# Mobo-v09.net
KiCad netlist of a schematic drawn in EAGLE
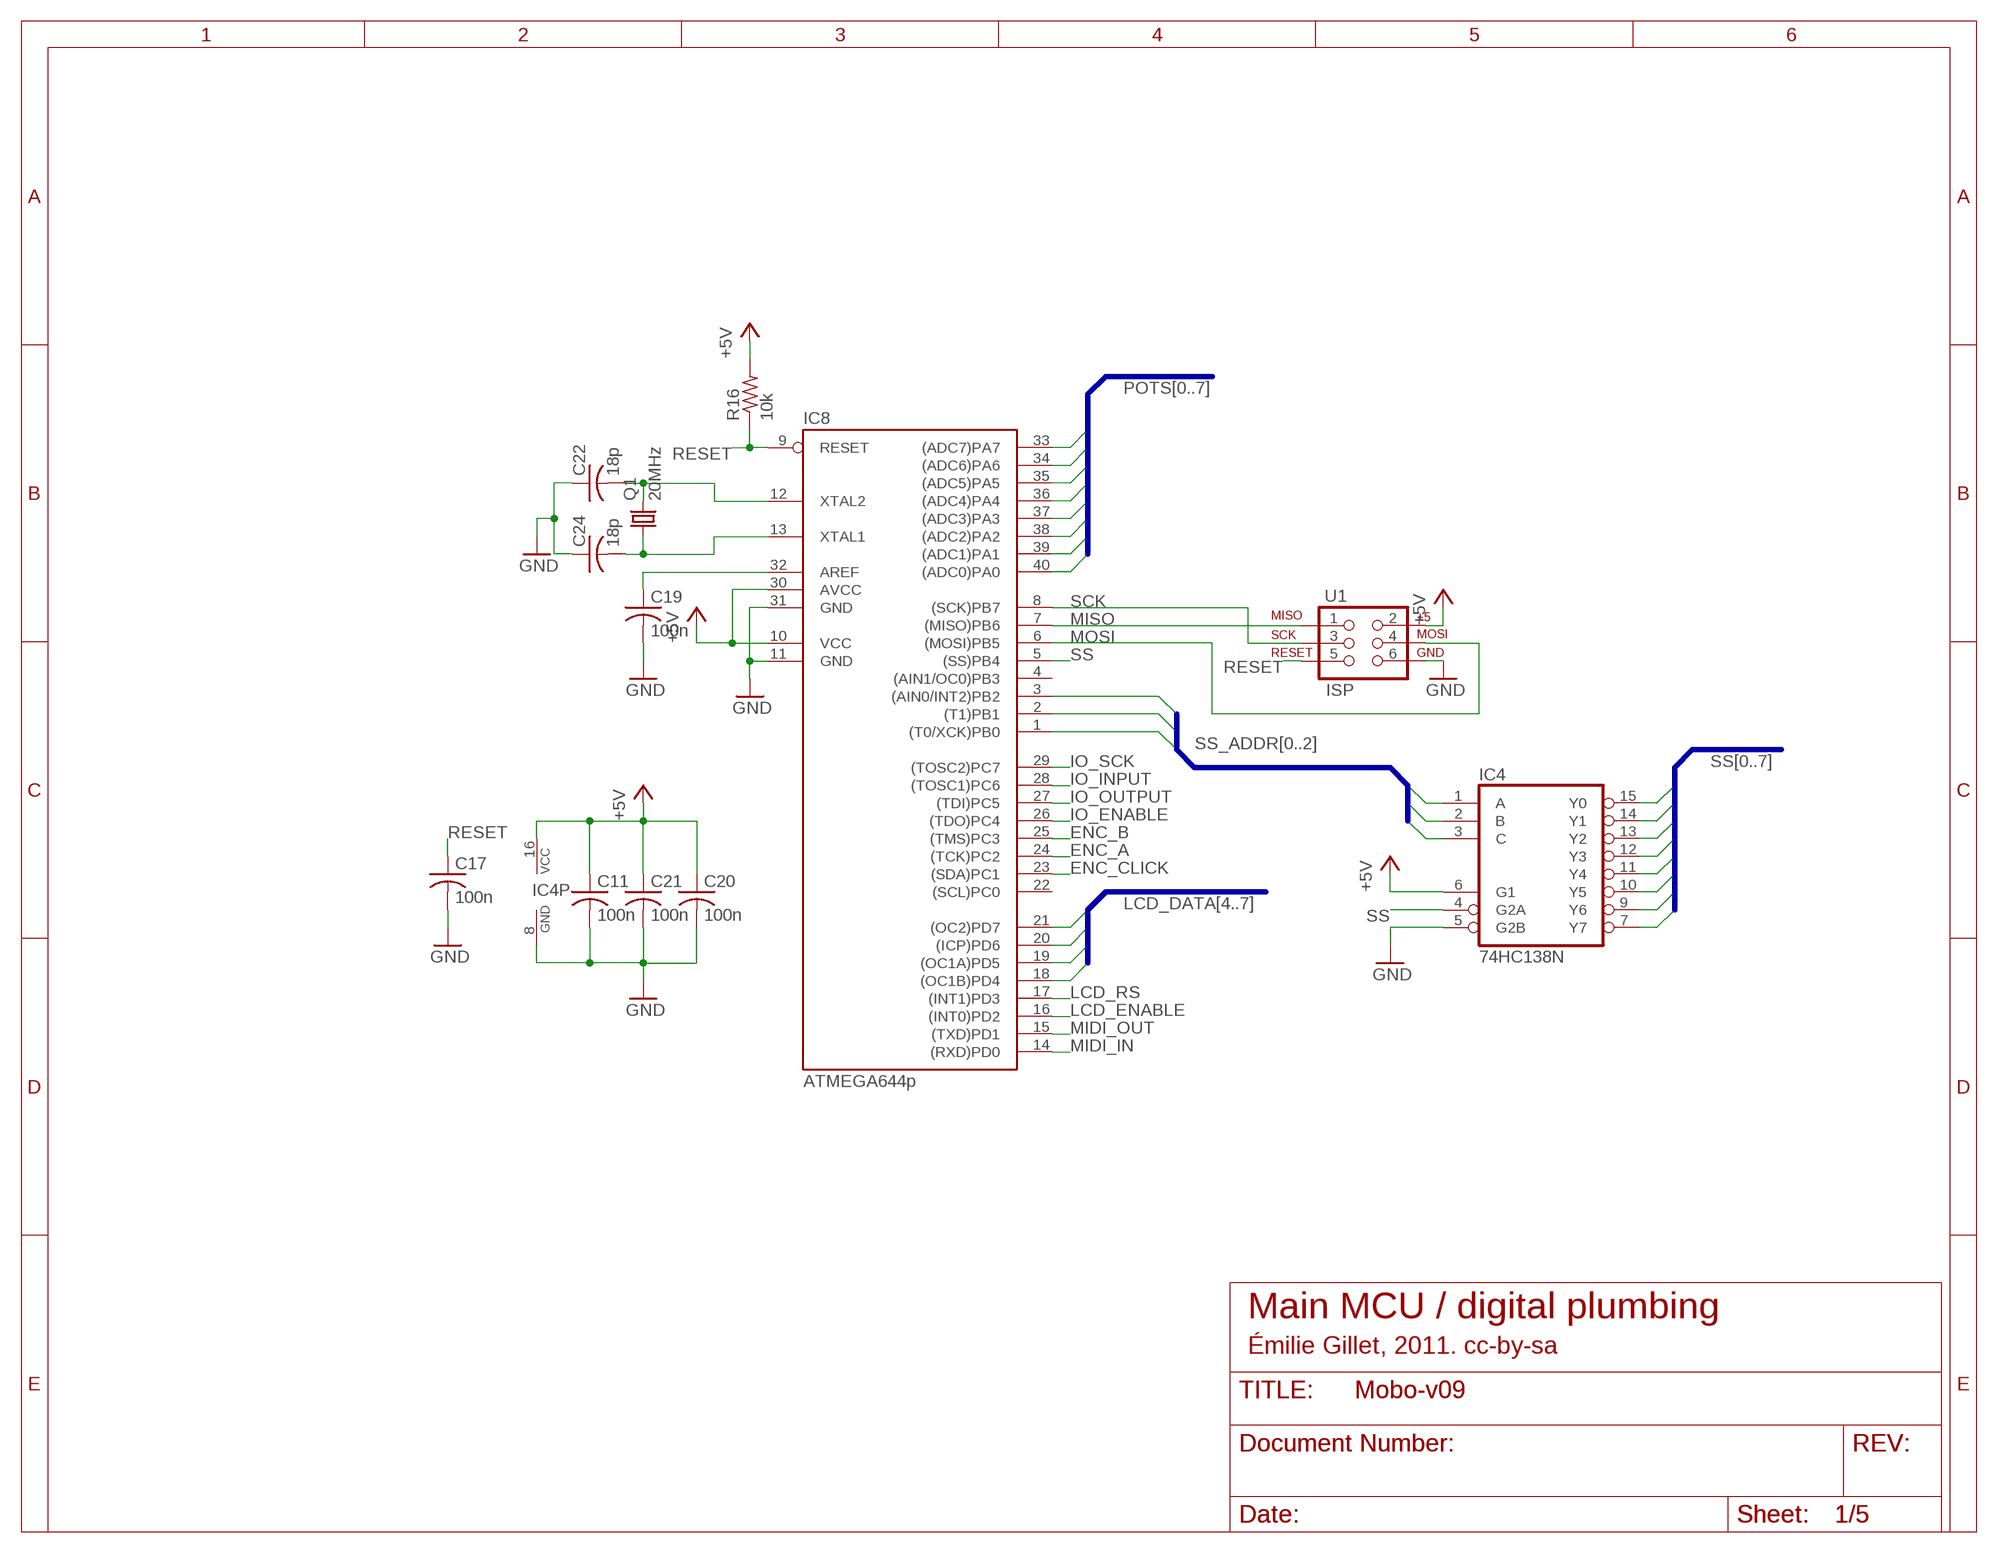
[diagram p0: schematic, sheet 1]
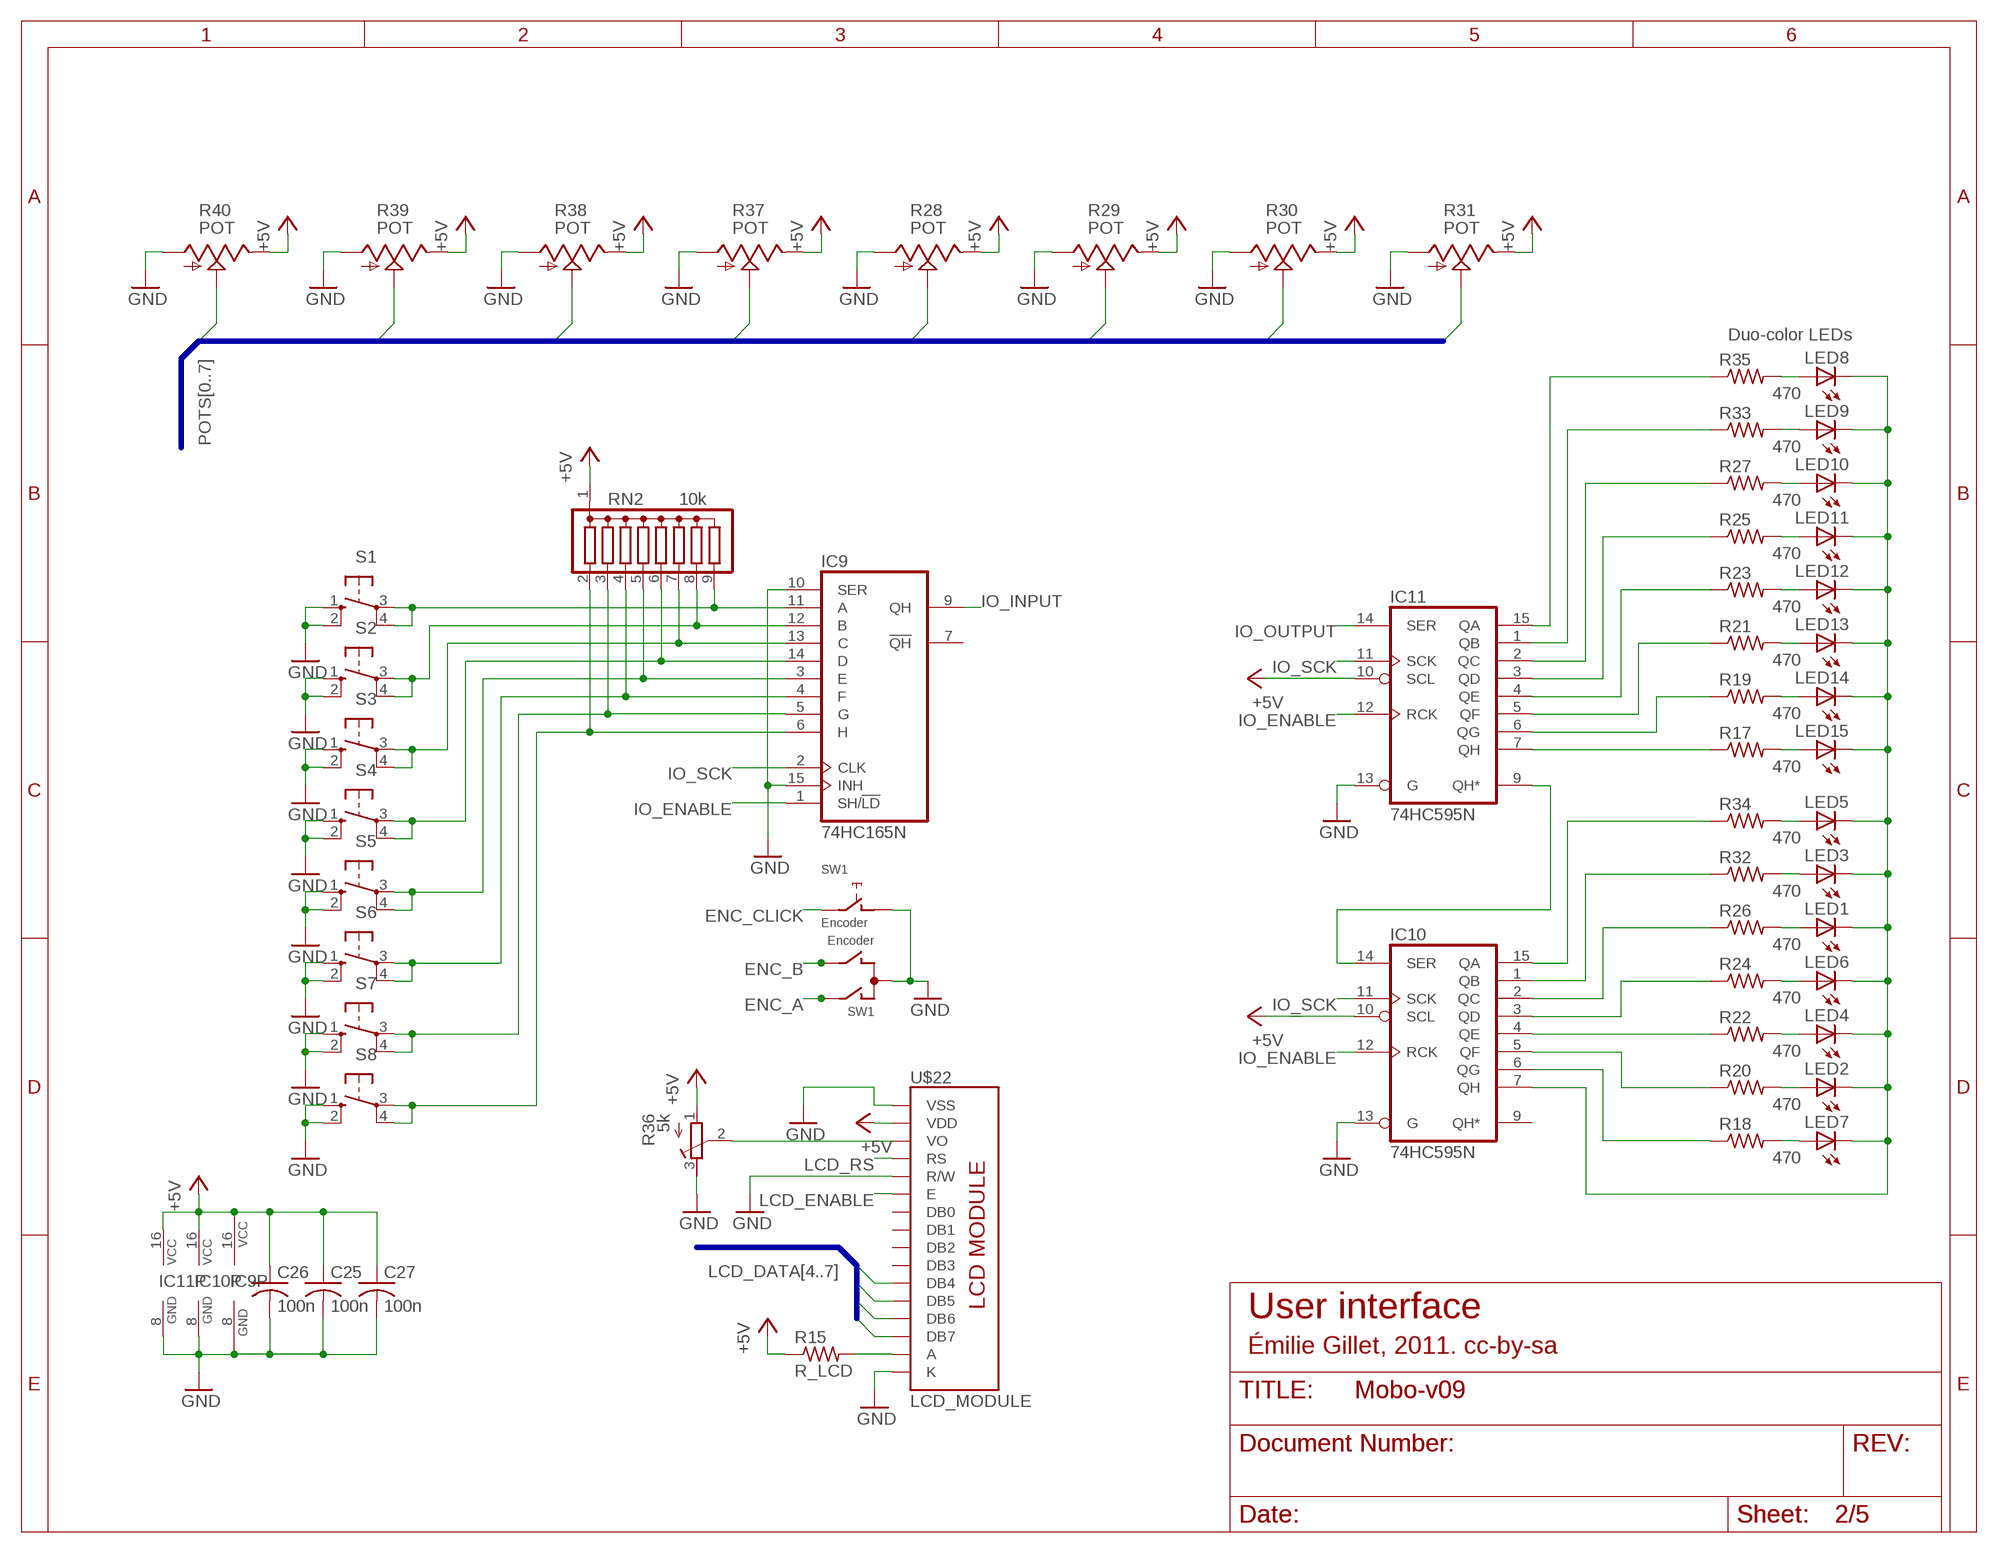
[diagram p1: schematic, sheet 2]
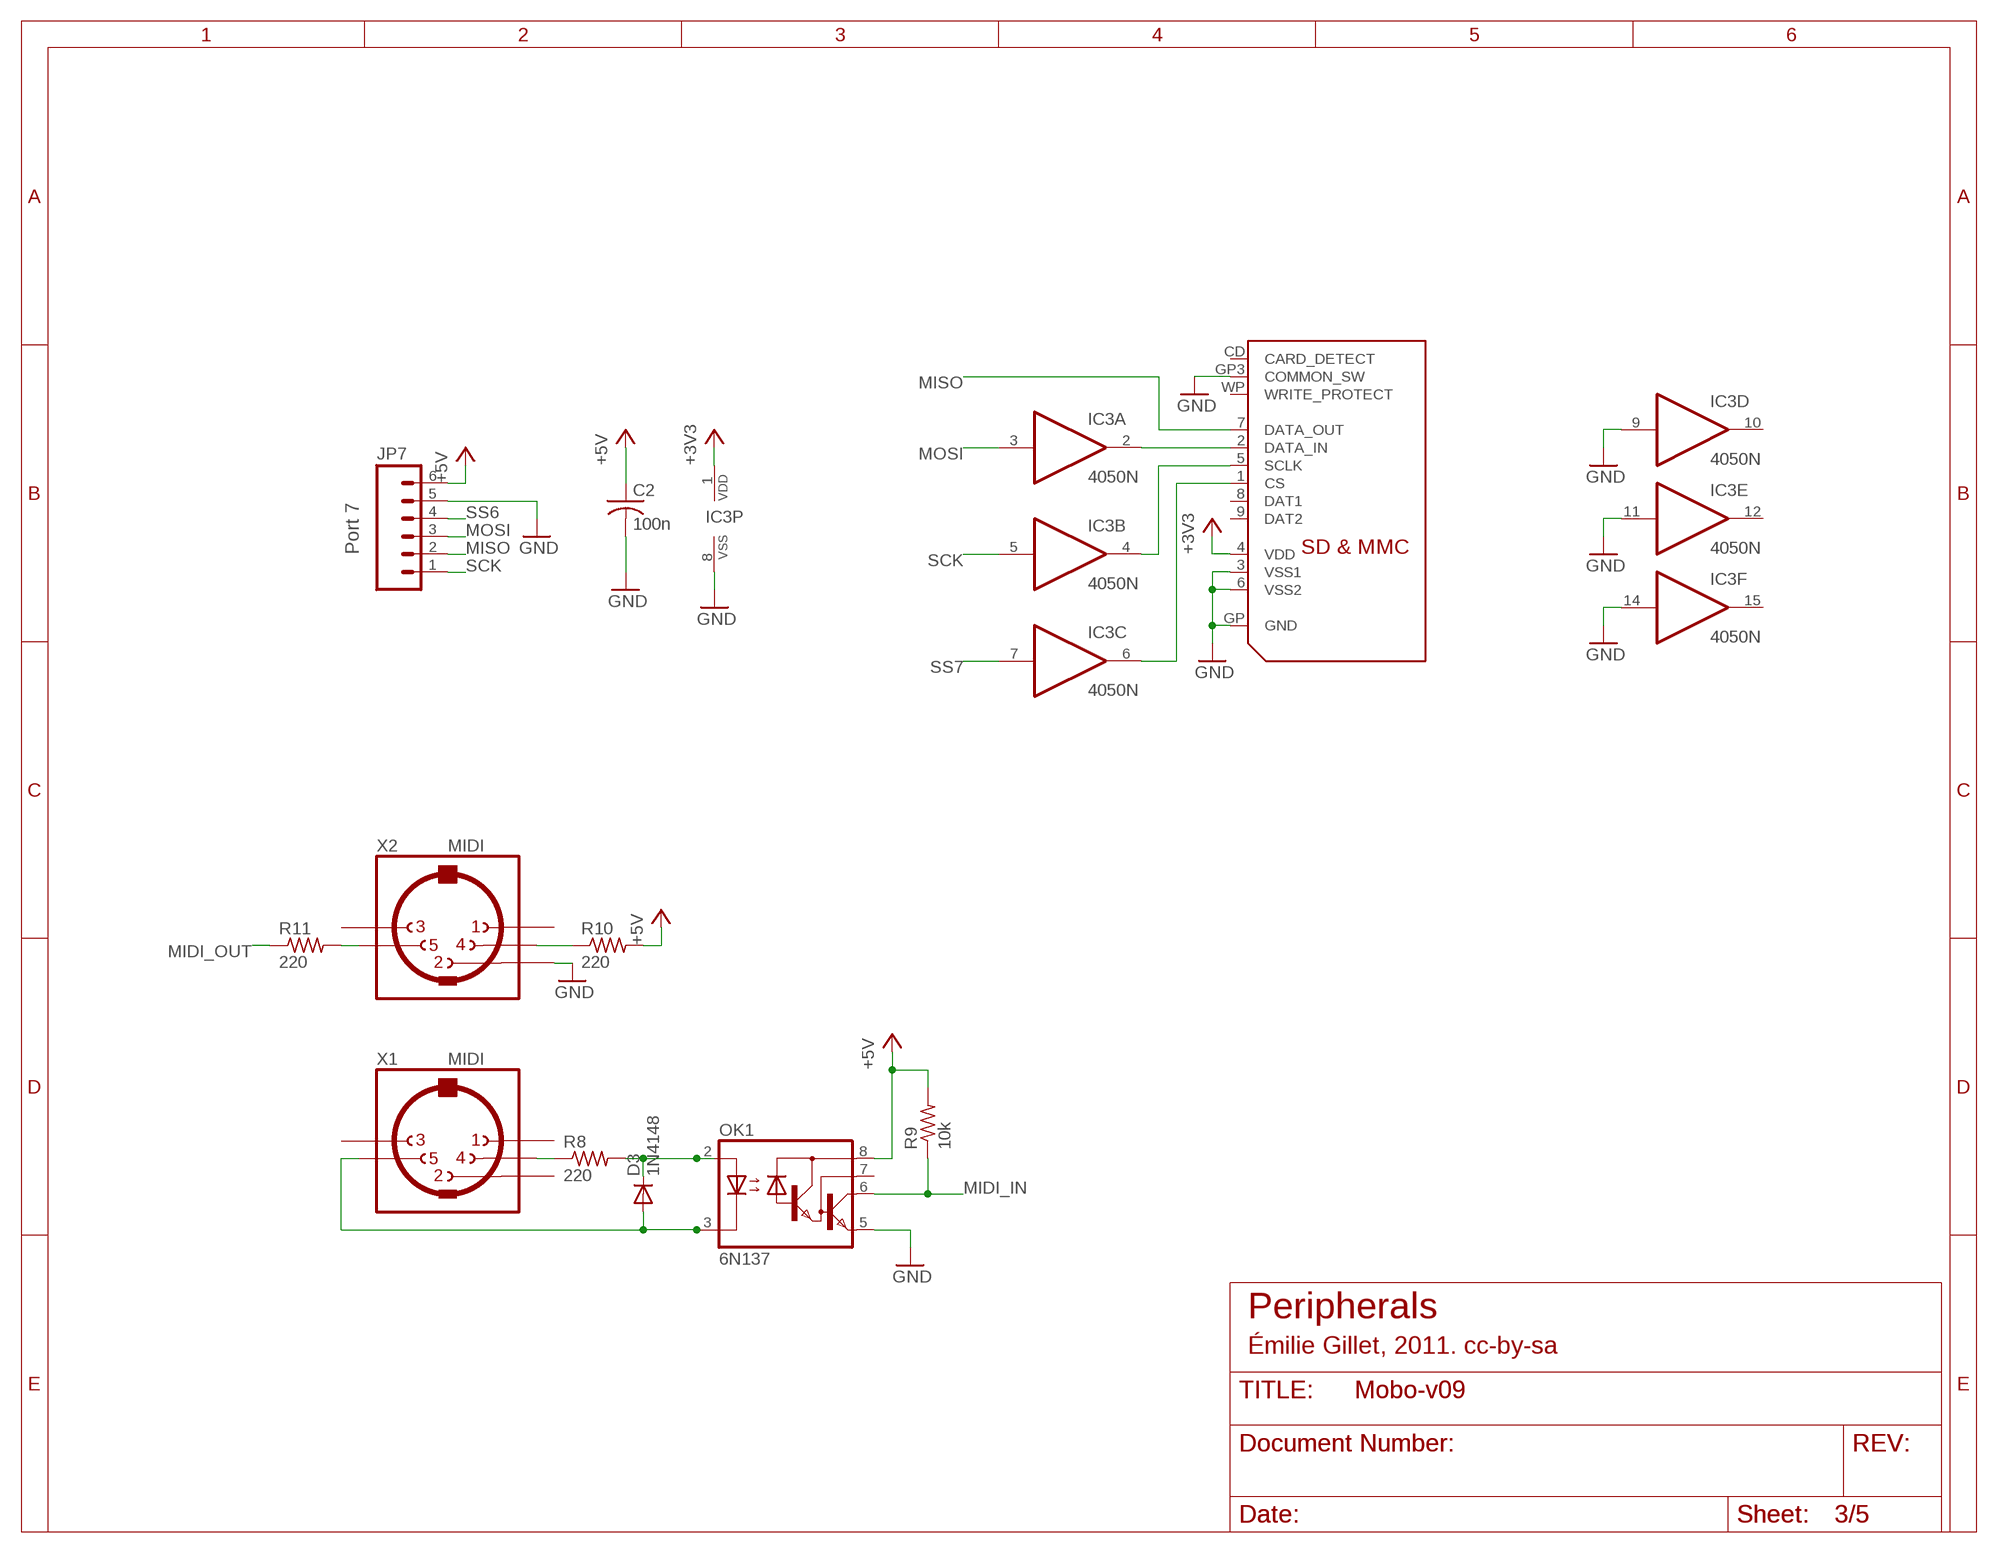
[diagram p2: schematic, sheet 3]
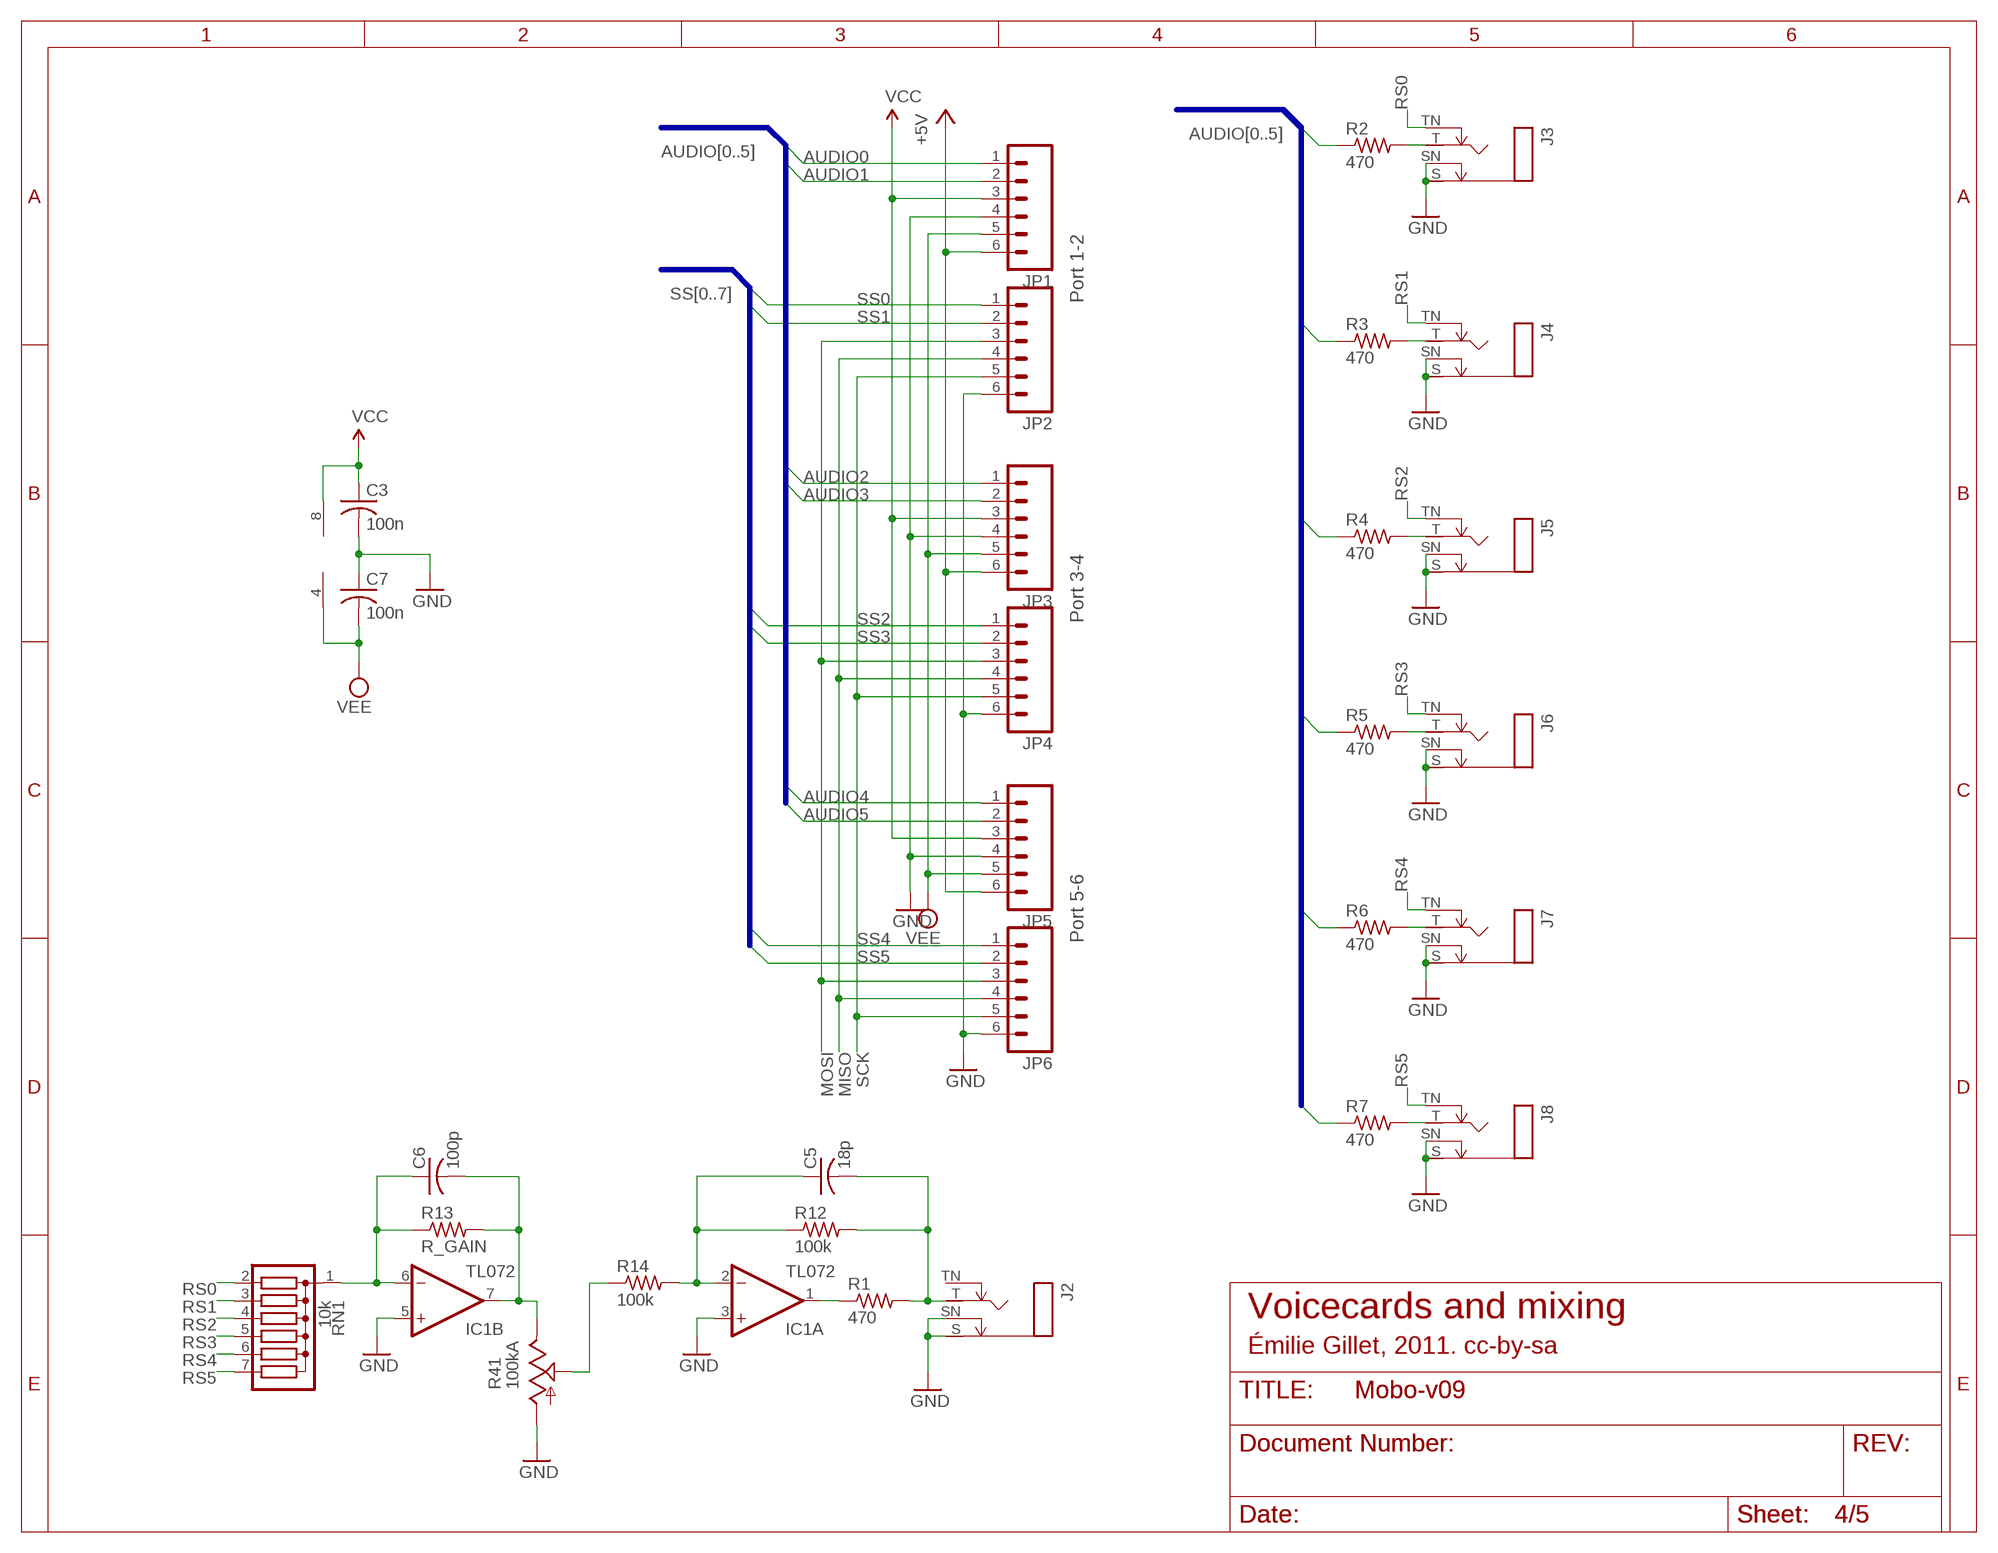
[diagram p3: schematic, sheet 4]
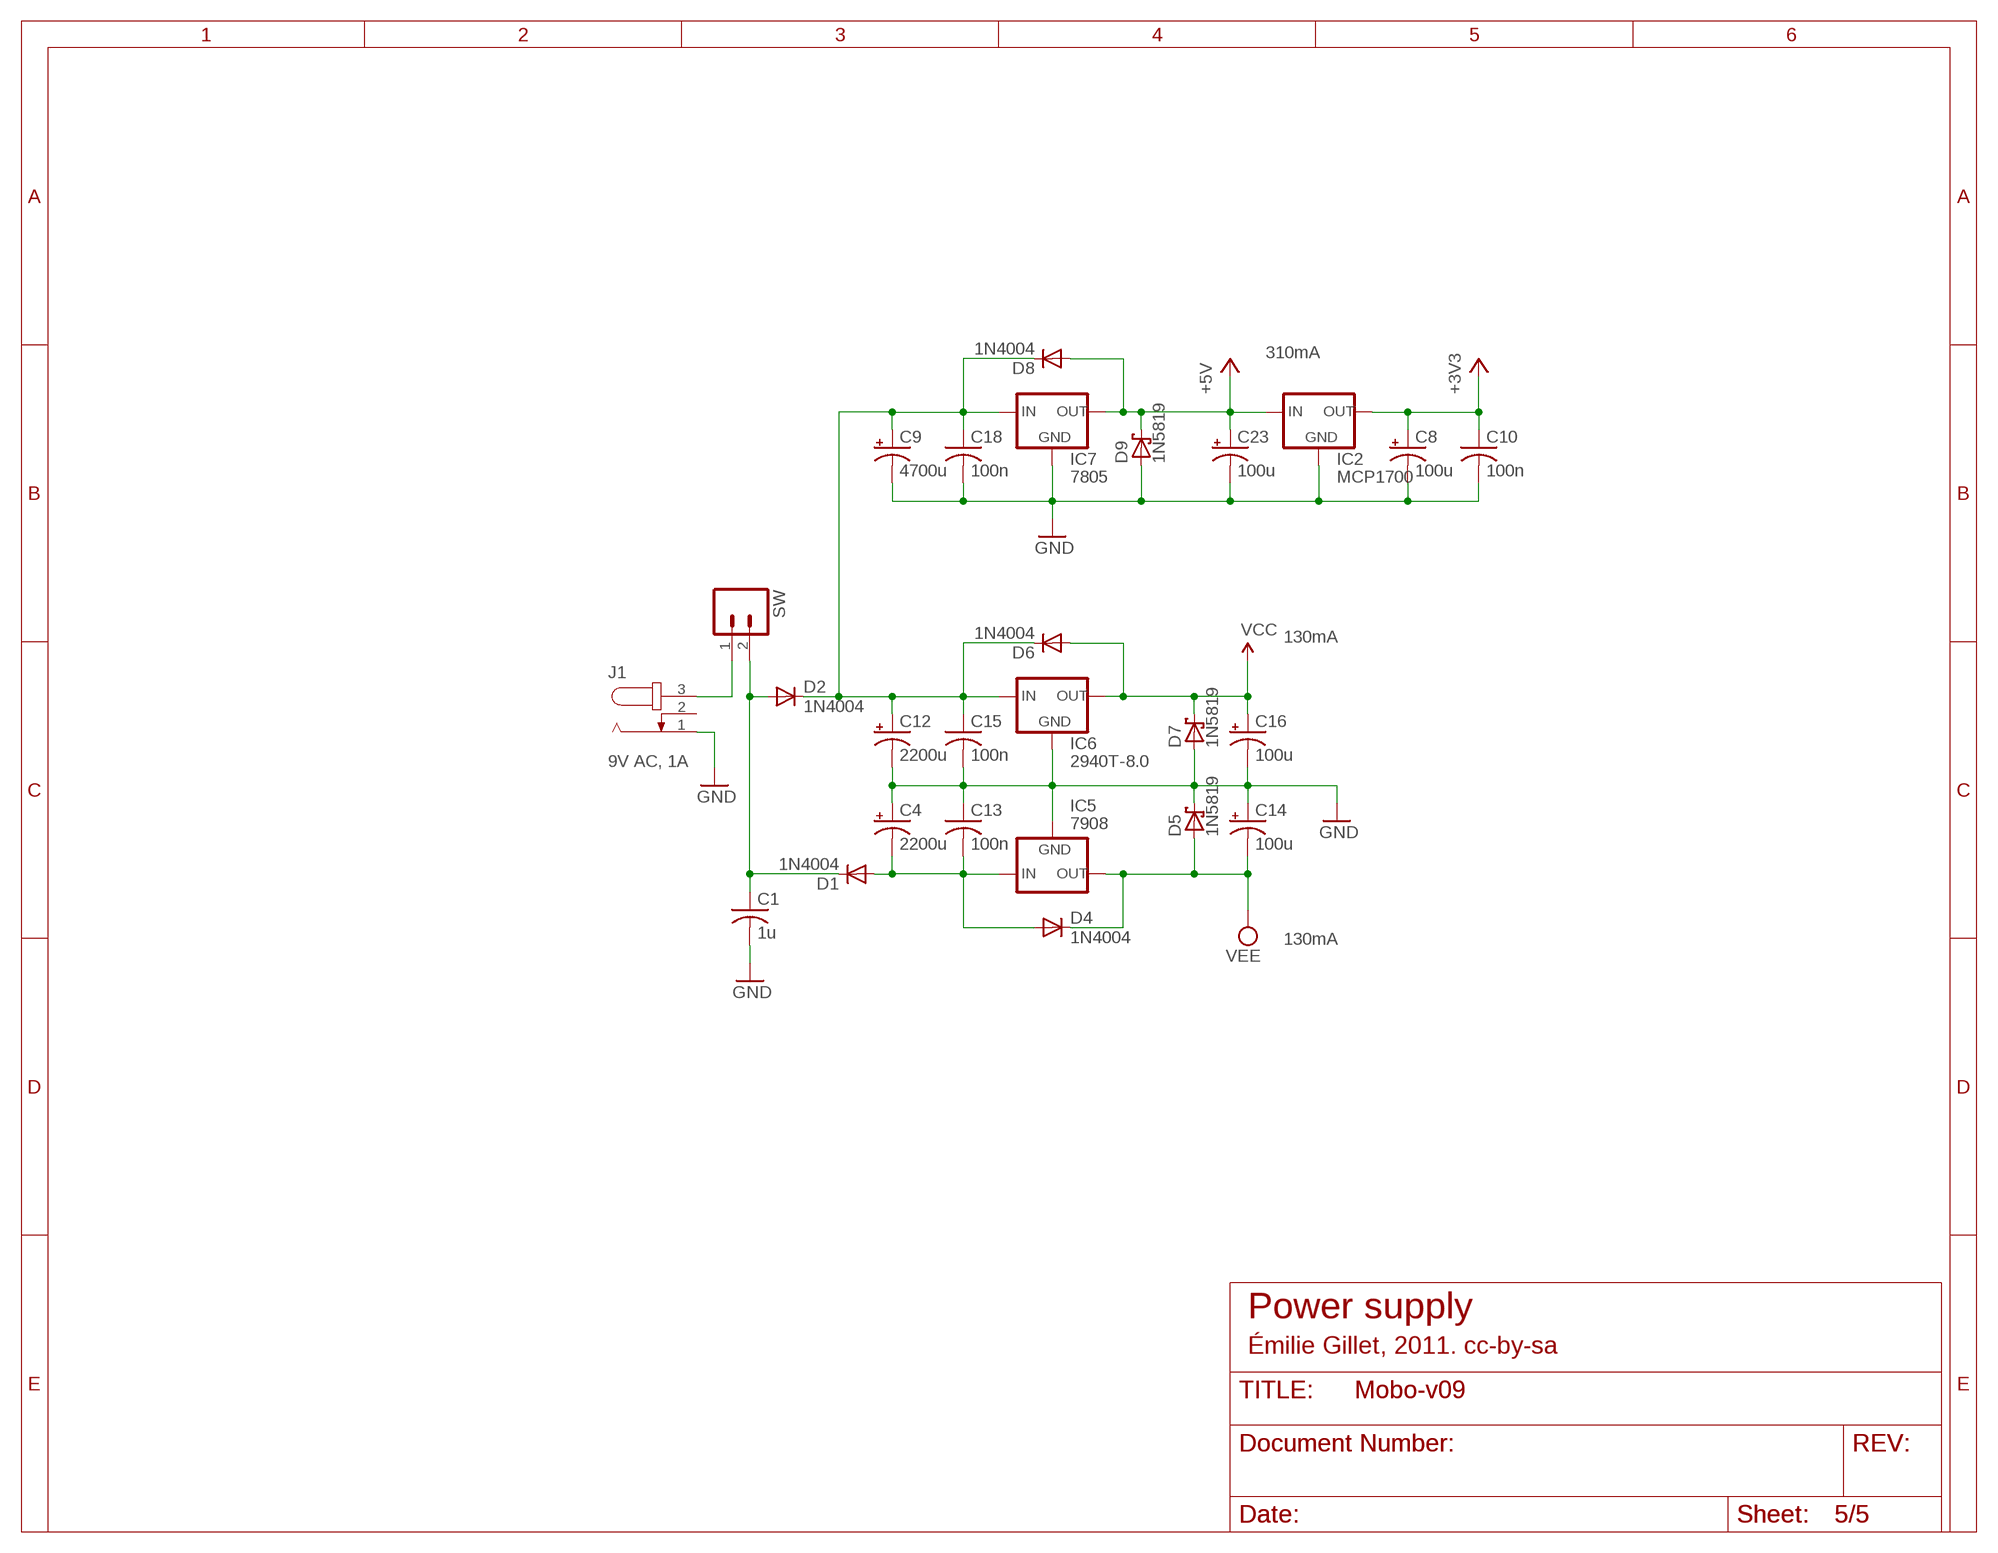
[diagram p4: schematic, sheet 5]

(export (version "E")
  (design (tool "Eeschema 10.0.6"))
  (components
    (comp (ref "C1")
      (value "1u")
      (footprint "eagle-import:C075-052X106")
      (libsource (lib "eagle-import") (part "C-US075-052X106"))
    )
    (comp (ref "C4")
      (value "2200u")
      (footprint "eagle-import:E5-13")
      (libsource (lib "eagle-import") (part "CPOL-USE5-13"))
    )
    (comp (ref "C8")
      (value "100u")
      (footprint "eagle-import:E2,5-7")
      (libsource (lib "eagle-import") (part "CPOL-USE2.5-7"))
    )
    (comp (ref "C9")
      (value "4700u")
      (footprint "eagle-import:E7,5-16")
      (libsource (lib "eagle-import") (part "CPOL-USE7.5-16"))
    )
    (comp (ref "C10")
      (value "100n")
      (footprint "eagle-import:C025-024X044")
      (libsource (lib "eagle-import") (part "C-US025-024X044"))
    )
    (comp (ref "C12")
      (value "2200u")
      (footprint "eagle-import:E5-13")
      (libsource (lib "eagle-import") (part "CPOL-USE5-13"))
    )
    (comp (ref "C13")
      (value "100n")
      (footprint "eagle-import:C025-025X050")
      (libsource (lib "eagle-import") (part "C-US025-025X050"))
    )
    (comp (ref "C14")
      (value "100u")
      (footprint "eagle-import:E2,5-7")
      (libsource (lib "eagle-import") (part "CPOL-USE2.5-7"))
    )
    (comp (ref "C15")
      (value "100n")
      (footprint "eagle-import:C025-025X050")
      (libsource (lib "eagle-import") (part "C-US025-025X050"))
    )
    (comp (ref "C16")
      (value "100u")
      (footprint "eagle-import:E2,5-7")
      (libsource (lib "eagle-import") (part "CPOL-USE2.5-7"))
    )
    (comp (ref "C18")
      (value "100n")
      (footprint "eagle-import:C025-025X050")
      (libsource (lib "eagle-import") (part "C-US025-025X050"))
    )
    (comp (ref "C23")
      (value "100u")
      (footprint "eagle-import:E2,5-7")
      (libsource (lib "eagle-import") (part "CPOL-USE2.5-7"))
    )
    (comp (ref "D1")
      (value "1N4004")
      (footprint "eagle-import:DO41-10")
      (libsource (lib "eagle-import") (part "1N4004"))
    )
    (comp (ref "D2")
      (value "1N4004")
      (footprint "eagle-import:DO41-10")
      (libsource (lib "eagle-import") (part "1N4004"))
    )
    (comp (ref "D4")
      (value "1N4004")
      (footprint "eagle-import:DO41-10")
      (libsource (lib "eagle-import") (part "1N4004"))
    )
    (comp (ref "D5")
      (value "1N5819")
      (footprint "eagle-import:DO41-7.6")
      (libsource (lib "eagle-import") (part "1N5819-T"))
    )
    (comp (ref "D6")
      (value "1N4004")
      (footprint "eagle-import:DO41-10")
      (libsource (lib "eagle-import") (part "1N4004"))
    )
    (comp (ref "D7")
      (value "1N5819")
      (footprint "eagle-import:DO41-7.6")
      (libsource (lib "eagle-import") (part "1N5819-T"))
    )
    (comp (ref "D8")
      (value "1N4004")
      (footprint "eagle-import:DO41-10")
      (libsource (lib "eagle-import") (part "1N4004"))
    )
    (comp (ref "D9")
      (value "1N5819")
      (footprint "eagle-import:DO41-7.6")
      (libsource (lib "eagle-import") (part "1N5819-T"))
    )
    (comp (ref "IC2")
      (value "MCP1700")
      (footprint "eagle-import:TO92-INLINE")
      (libsource (lib "eagle-import") (part "MCP1700INLINE"))
    )
    (comp (ref "IC5")
      (value "7908")
      (footprint "eagle-import:79XXS")
      (libsource (lib "eagle-import") (part "79XXS"))
    )
    (comp (ref "IC6")
      (value "2940T-8.0")
      (footprint "eagle-import:78XXL")
      (libsource (lib "eagle-import") (part "78XXL"))
    )
    (comp (ref "IC7")
      (value "7805")
      (footprint "eagle-import:78XXS")
      (libsource (lib "eagle-import") (part "78XXS"))
    )
    (comp (ref "J1")
      (value "JACK-PLUG2")
      (footprint "eagle-import:SPC4078_BIG_HOLES")
      (libsource (lib "eagle-import") (part "JACK-PLUG2"))
    )
    (comp (ref "SW")
      (value "M02PTH")
      (footprint "eagle-import:1X02")
      (libsource (lib "eagle-import") (part "M02PTH"))
    )
    (comp (ref "C11")
      (value "100n")
      (footprint "eagle-import:C025-024X044")
      (libsource (lib "eagle-import") (part "C-US025-024X044"))
    )
    (comp (ref "C17")
      (value "100n")
      (footprint "eagle-import:C025-024X044")
      (libsource (lib "eagle-import") (part "C-US025-024X044"))
    )
    (comp (ref "C19")
      (value "100n")
      (footprint "eagle-import:C025-024X044")
      (libsource (lib "eagle-import") (part "C-US025-024X044"))
    )
    (comp (ref "C20")
      (value "100n")
      (footprint "eagle-import:C025-024X044")
      (libsource (lib "eagle-import") (part "C-US025-024X044"))
    )
    (comp (ref "C21")
      (value "100n")
      (footprint "eagle-import:C025-024X044")
      (libsource (lib "eagle-import") (part "C-US025-024X044"))
    )
    (comp (ref "C22")
      (value "18p")
      (footprint "eagle-import:C025-024X044")
      (libsource (lib "eagle-import") (part "C-US025-024X044"))
    )
    (comp (ref "C24")
      (value "18p")
      (footprint "eagle-import:C025-024X044")
      (libsource (lib "eagle-import") (part "C-US025-024X044"))
    )
    (comp (ref "IC4")
      (value "74HC138N")
      (footprint "eagle-import:DIL16")
      (libsource (lib "eagle-import") (part "74138NHC"))
    )
    (comp (ref "IC8")
      (value "ATMEGA644p")
      (footprint "eagle-import:DIL40")
      (libsource (lib "eagle-import") (part "MEGA16-P"))
    )
    (comp (ref "Q1")
      (value "20MHz")
      (footprint "eagle-import:HC49U-V")
      (libsource (lib "eagle-import") (part "CRYSTALHC49U-V"))
    )
    (comp (ref "R16")
      (value "10k")
      (footprint "eagle-import:0204_7")
      (libsource (lib "eagle-import") (part "R-US_0204/7"))
    )
    (comp (ref "U1")
      (value "ISP")
      (footprint "eagle-import:2X3")
      (libsource (lib "eagle-import") (part "AVR_SPI_PRG_6PTH"))
    )
    (comp (ref "C25")
      (value "100n")
      (footprint "eagle-import:C025-024X044")
      (libsource (lib "eagle-import") (part "C-US025-024X044"))
    )
    (comp (ref "C26")
      (value "100n")
      (footprint "eagle-import:C025-024X044")
      (libsource (lib "eagle-import") (part "C-US025-024X044"))
    )
    (comp (ref "C27")
      (value "100n")
      (footprint "eagle-import:C025-024X044")
      (libsource (lib "eagle-import") (part "C-US025-024X044"))
    )
    (comp (ref "IC9")
      (value "74HC165N")
      (footprint "eagle-import:DIL16")
      (libsource (lib "eagle-import") (part "74165NLS"))
    )
    (comp (ref "IC10")
      (value "74HC595N")
      (footprint "eagle-import:DIL16")
      (libsource (lib "eagle-import") (part "74595NHC"))
    )
    (comp (ref "IC11")
      (value "74HC595N")
      (footprint "eagle-import:DIL16")
      (libsource (lib "eagle-import") (part "74595NHC"))
    )
    (comp (ref "LED1")
      (value "LED3MM")
      (footprint "eagle-import:LED3MM")
      (libsource (lib "eagle-import") (part "LED3MM"))
    )
    (comp (ref "LED2")
      (value "LED3MM")
      (footprint "eagle-import:LED3MM")
      (libsource (lib "eagle-import") (part "LED3MM"))
    )
    (comp (ref "LED3")
      (value "LED3MM")
      (footprint "eagle-import:LED3MM")
      (libsource (lib "eagle-import") (part "LED3MM"))
    )
    (comp (ref "LED4")
      (value "LED3MM")
      (footprint "eagle-import:LED3MM")
      (libsource (lib "eagle-import") (part "LED3MM"))
    )
    (comp (ref "LED5")
      (value "LED3MM")
      (footprint "eagle-import:LED3MM")
      (libsource (lib "eagle-import") (part "LED3MM"))
    )
    (comp (ref "LED6")
      (value "LED3MM")
      (footprint "eagle-import:LED3MM")
      (libsource (lib "eagle-import") (part "LED3MM"))
    )
    (comp (ref "LED7")
      (value "LED3MM")
      (footprint "eagle-import:LED3MM")
      (libsource (lib "eagle-import") (part "LED3MM"))
    )
    (comp (ref "LED8")
      (value "LED3MM")
      (footprint "eagle-import:LED3MM")
      (libsource (lib "eagle-import") (part "LED3MM"))
    )
    (comp (ref "LED9")
      (value "LED3MM")
      (footprint "eagle-import:LED3MM")
      (libsource (lib "eagle-import") (part "LED3MM"))
    )
    (comp (ref "LED10")
      (value "LED3MM")
      (footprint "eagle-import:LED3MM")
      (libsource (lib "eagle-import") (part "LED3MM"))
    )
    (comp (ref "LED11")
      (value "LED3MM")
      (footprint "eagle-import:LED3MM")
      (libsource (lib "eagle-import") (part "LED3MM"))
    )
    (comp (ref "LED12")
      (value "LED3MM")
      (footprint "eagle-import:LED3MM")
      (libsource (lib "eagle-import") (part "LED3MM"))
    )
    (comp (ref "LED13")
      (value "LED3MM")
      (footprint "eagle-import:LED3MM")
      (libsource (lib "eagle-import") (part "LED3MM"))
    )
    (comp (ref "LED14")
      (value "LED3MM")
      (footprint "eagle-import:LED3MM")
      (libsource (lib "eagle-import") (part "LED3MM"))
    )
    (comp (ref "LED15")
      (value "LED3MM")
      (footprint "eagle-import:LED3MM")
      (libsource (lib "eagle-import") (part "LED3MM"))
    )
    (comp (ref "R15")
      (value "R_LCD")
      (footprint "eagle-import:0204_7")
      (libsource (lib "eagle-import") (part "R-US_0204/7"))
    )
    (comp (ref "R17")
      (value "470")
      (footprint "eagle-import:0204_7")
      (libsource (lib "eagle-import") (part "R-US_0204/7"))
    )
    (comp (ref "R18")
      (value "470")
      (footprint "eagle-import:0204_7")
      (libsource (lib "eagle-import") (part "R-US_0204/7"))
    )
    (comp (ref "R19")
      (value "470")
      (footprint "eagle-import:0204_7")
      (libsource (lib "eagle-import") (part "R-US_0204/7"))
    )
    (comp (ref "R20")
      (value "470")
      (footprint "eagle-import:0204_7")
      (libsource (lib "eagle-import") (part "R-US_0204/7"))
    )
    (comp (ref "R21")
      (value "470")
      (footprint "eagle-import:0204_7")
      (libsource (lib "eagle-import") (part "R-US_0204/7"))
    )
    (comp (ref "R22")
      (value "470")
      (footprint "eagle-import:0204_7")
      (libsource (lib "eagle-import") (part "R-US_0204/7"))
    )
    (comp (ref "R23")
      (value "470")
      (footprint "eagle-import:0204_7")
      (libsource (lib "eagle-import") (part "R-US_0204/7"))
    )
    (comp (ref "R24")
      (value "470")
      (footprint "eagle-import:0204_7")
      (libsource (lib "eagle-import") (part "R-US_0204/7"))
    )
    (comp (ref "R25")
      (value "470")
      (footprint "eagle-import:0204_7")
      (libsource (lib "eagle-import") (part "R-US_0204/7"))
    )
    (comp (ref "R26")
      (value "470")
      (footprint "eagle-import:0204_7")
      (libsource (lib "eagle-import") (part "R-US_0204/7"))
    )
    (comp (ref "R27")
      (value "470")
      (footprint "eagle-import:0204_7")
      (libsource (lib "eagle-import") (part "R-US_0204/7"))
    )
    (comp (ref "R28")
      (value "POT")
      (footprint "eagle-import:ALPS_POT_VERTICAL")
      (libsource (lib "eagle-import") (part "POT_USVERTICAL"))
    )
    (comp (ref "R29")
      (value "POT")
      (footprint "eagle-import:ALPS_POT_VERTICAL")
      (libsource (lib "eagle-import") (part "POT_USVERTICAL"))
    )
    (comp (ref "R30")
      (value "POT")
      (footprint "eagle-import:ALPS_POT_VERTICAL")
      (libsource (lib "eagle-import") (part "POT_USVERTICAL"))
    )
    (comp (ref "R31")
      (value "POT")
      (footprint "eagle-import:ALPS_POT_VERTICAL")
      (libsource (lib "eagle-import") (part "POT_USVERTICAL"))
    )
    (comp (ref "R32")
      (value "470")
      (footprint "eagle-import:0204_7")
      (libsource (lib "eagle-import") (part "R-US_0204/7"))
    )
    (comp (ref "R33")
      (value "470")
      (footprint "eagle-import:0204_7")
      (libsource (lib "eagle-import") (part "R-US_0204/7"))
    )
    (comp (ref "R34")
      (value "470")
      (footprint "eagle-import:0204_7")
      (libsource (lib "eagle-import") (part "R-US_0204/7"))
    )
    (comp (ref "R35")
      (value "470")
      (footprint "eagle-import:0204_7")
      (libsource (lib "eagle-import") (part "R-US_0204/7"))
    )
    (comp (ref "R36")
      (value "5k")
      (footprint "eagle-import:RTRIM3339P")
      (libsource (lib "eagle-import") (part "R-TRIMM3339P"))
    )
    (comp (ref "R37")
      (value "POT")
      (footprint "eagle-import:ALPS_POT_VERTICAL")
      (libsource (lib "eagle-import") (part "POT_USVERTICAL"))
    )
    (comp (ref "R38")
      (value "POT")
      (footprint "eagle-import:ALPS_POT_VERTICAL")
      (libsource (lib "eagle-import") (part "POT_USVERTICAL"))
    )
    (comp (ref "R39")
      (value "POT")
      (footprint "eagle-import:ALPS_POT_VERTICAL")
      (libsource (lib "eagle-import") (part "POT_USVERTICAL"))
    )
    (comp (ref "R40")
      (value "POT")
      (footprint "eagle-import:ALPS_POT_VERTICAL")
      (libsource (lib "eagle-import") (part "POT_USVERTICAL"))
    )
    (comp (ref "RN2")
      (value "10k")
      (footprint "eagle-import:SIL9")
      (libsource (lib "eagle-import") (part "G08R"))
    )
    (comp (ref "S1")
      (value "40-XX")
      (footprint "eagle-import:B3F-40XX")
      (libsource (lib "eagle-import") (part "40-XX"))
    )
    (comp (ref "S2")
      (value "40-XX")
      (footprint "eagle-import:B3F-40XX")
      (libsource (lib "eagle-import") (part "40-XX"))
    )
    (comp (ref "S3")
      (value "40-XX")
      (footprint "eagle-import:B3F-40XX")
      (libsource (lib "eagle-import") (part "40-XX"))
    )
    (comp (ref "S4")
      (value "40-XX")
      (footprint "eagle-import:B3F-40XX")
      (libsource (lib "eagle-import") (part "40-XX"))
    )
    (comp (ref "S5")
      (value "40-XX")
      (footprint "eagle-import:B3F-40XX")
      (libsource (lib "eagle-import") (part "40-XX"))
    )
    (comp (ref "S6")
      (value "40-XX")
      (footprint "eagle-import:B3F-40XX")
      (libsource (lib "eagle-import") (part "40-XX"))
    )
    (comp (ref "S7")
      (value "40-XX")
      (footprint "eagle-import:B3F-40XX")
      (libsource (lib "eagle-import") (part "40-XX"))
    )
    (comp (ref "S8")
      (value "40-XX")
      (footprint "eagle-import:B3F-40XX")
      (libsource (lib "eagle-import") (part "40-XX"))
    )
    (comp (ref "SW1")
      (value "Encoder")
      (footprint "eagle-import:ALPS_EC12E_SW")
      (libsource (lib "eagle-import") (part "EC12E_SW"))
    )
    (comp (ref "U$22")
      (value "LCD_MODULE")
      (footprint "eagle-import:LCD_MODULE_2X40")
      (libsource (lib "eagle-import") (part "LCD_MODULE"))
    )
    (comp (ref "C2")
      (value "100n")
      (footprint "eagle-import:C025-024X044")
      (libsource (lib "eagle-import") (part "C-US025-024X044"))
    )
    (comp (ref "D3")
      (value "1N4148")
      (footprint "eagle-import:D-5")
      (libsource (lib "eagle-import") (part "DIODE-D-5"))
    )
    (comp (ref "IC3")
      (value "4050N")
      (footprint "eagle-import:DIL16")
      (libsource (lib "eagle-import") (part "4050N"))
    )
    (comp (ref "JP7")
      (value "M06SIP")
      (footprint "eagle-import:1X06")
      (libsource (lib "eagle-import") (part "M06SIP"))
    )
    (comp (ref "OK1")
      (value "6N137")
      (footprint "eagle-import:DIL08")
      (libsource (lib "eagle-import") (part "6N138"))
    )
    (comp (ref "R8")
      (value "220")
      (footprint "eagle-import:0204_7")
      (libsource (lib "eagle-import") (part "R-US_0204/7"))
    )
    (comp (ref "R9")
      (value "10k")
      (footprint "eagle-import:0204_7")
      (libsource (lib "eagle-import") (part "R-US_0204/7"))
    )
    (comp (ref "R10")
      (value "220")
      (footprint "eagle-import:0204_7")
      (libsource (lib "eagle-import") (part "R-US_0204/7"))
    )
    (comp (ref "R11")
      (value "220")
      (footprint "eagle-import:0204_7")
      (libsource (lib "eagle-import") (part "R-US_0204/7"))
    )
    (comp (ref "U$26")
      (value "SDMMC06132")
      (footprint "eagle-import:06132")
      (libsource (lib "eagle-import") (part "SDMMC06132"))
    )
    (comp (ref "X1")
      (value "MIDI")
      (footprint "eagle-import:MAB5SH")
      (libsource (lib "eagle-import") (part "MAB5SH"))
    )
    (comp (ref "X2")
      (value "MIDI")
      (footprint "eagle-import:MAB5SH")
      (libsource (lib "eagle-import") (part "MAB5SH"))
    )
    (comp (ref "C3")
      (value "100n")
      (footprint "eagle-import:C025-024X044")
      (libsource (lib "eagle-import") (part "C-US025-024X044"))
    )
    (comp (ref "C5")
      (value "18p")
      (footprint "eagle-import:C025-024X044")
      (libsource (lib "eagle-import") (part "C-US025-024X044"))
    )
    (comp (ref "C6")
      (value "100p")
      (footprint "eagle-import:C025-024X044")
      (libsource (lib "eagle-import") (part "C-US025-024X044"))
    )
    (comp (ref "C7")
      (value "100n")
      (footprint "eagle-import:C025-024X044")
      (libsource (lib "eagle-import") (part "C-US025-024X044"))
    )
    (comp (ref "IC1")
      (value "TL072")
      (footprint "eagle-import:DIL08")
      (libsource (lib "eagle-import") (part "TL072P"))
    )
    (comp (ref "J2")
      (value "MONOSWSLIM")
      (footprint "eagle-import:NRJ4HF")
      (libsource (lib "eagle-import") (part "MONOSWSLIM"))
    )
    (comp (ref "J3")
      (value "MONOSWSLIM")
      (footprint "eagle-import:NRJ4HF")
      (libsource (lib "eagle-import") (part "MONOSWSLIM"))
    )
    (comp (ref "J4")
      (value "MONOSWSLIM")
      (footprint "eagle-import:NRJ4HF")
      (libsource (lib "eagle-import") (part "MONOSWSLIM"))
    )
    (comp (ref "J5")
      (value "MONOSWSLIM")
      (footprint "eagle-import:NRJ4HF")
      (libsource (lib "eagle-import") (part "MONOSWSLIM"))
    )
    (comp (ref "J6")
      (value "MONOSWSLIM")
      (footprint "eagle-import:NRJ4HF")
      (libsource (lib "eagle-import") (part "MONOSWSLIM"))
    )
    (comp (ref "J7")
      (value "MONOSWSLIM")
      (footprint "eagle-import:NRJ4HF")
      (libsource (lib "eagle-import") (part "MONOSWSLIM"))
    )
    (comp (ref "J8")
      (value "MONOSWSLIM")
      (footprint "eagle-import:NRJ4HF")
      (libsource (lib "eagle-import") (part "MONOSWSLIM"))
    )
    (comp (ref "JP1")
      (value "M06SIP")
      (footprint "eagle-import:1X06")
      (libsource (lib "eagle-import") (part "M06SIP"))
    )
    (comp (ref "JP2")
      (value "M06SIP")
      (footprint "eagle-import:1X06")
      (libsource (lib "eagle-import") (part "M06SIP"))
    )
    (comp (ref "JP3")
      (value "M06SIP")
      (footprint "eagle-import:1X06")
      (libsource (lib "eagle-import") (part "M06SIP"))
    )
    (comp (ref "JP4")
      (value "M06SIP")
      (footprint "eagle-import:1X06")
      (libsource (lib "eagle-import") (part "M06SIP"))
    )
    (comp (ref "JP5")
      (value "M06SIP")
      (footprint "eagle-import:1X06")
      (libsource (lib "eagle-import") (part "M06SIP"))
    )
    (comp (ref "JP6")
      (value "M06SIP")
      (footprint "eagle-import:1X06")
      (libsource (lib "eagle-import") (part "M06SIP"))
    )
    (comp (ref "R1")
      (value "470")
      (footprint "eagle-import:0204_7")
      (libsource (lib "eagle-import") (part "R-US_0204/7"))
    )
    (comp (ref "R2")
      (value "470")
      (footprint "eagle-import:0204_7")
      (libsource (lib "eagle-import") (part "R-US_0204/7"))
    )
    (comp (ref "R3")
      (value "470")
      (footprint "eagle-import:0204_7")
      (libsource (lib "eagle-import") (part "R-US_0204/7"))
    )
    (comp (ref "R4")
      (value "470")
      (footprint "eagle-import:0204_7")
      (libsource (lib "eagle-import") (part "R-US_0204/7"))
    )
    (comp (ref "R5")
      (value "470")
      (footprint "eagle-import:0204_7")
      (libsource (lib "eagle-import") (part "R-US_0204/7"))
    )
    (comp (ref "R6")
      (value "470")
      (footprint "eagle-import:0204_7")
      (libsource (lib "eagle-import") (part "R-US_0204/7"))
    )
    (comp (ref "R7")
      (value "470")
      (footprint "eagle-import:0204_7")
      (libsource (lib "eagle-import") (part "R-US_0204/7"))
    )
    (comp (ref "R12")
      (value "100k")
      (footprint "eagle-import:0204_7")
      (libsource (lib "eagle-import") (part "R-US_0204/7"))
    )
    (comp (ref "R13")
      (value "R_GAIN")
      (footprint "eagle-import:0204_7")
      (libsource (lib "eagle-import") (part "R-US_0204/7"))
    )
    (comp (ref "R14")
      (value "100k")
      (footprint "eagle-import:0204_7")
      (libsource (lib "eagle-import") (part "R-US_0204/7"))
    )
    (comp (ref "R41")
      (value "100kA")
      (footprint "eagle-import:ALPS_POT_VERTICAL")
      (libsource (lib "eagle-import") (part "POT_USVERTICAL"))
    )
    (comp (ref "RN1")
      (value "10k")
      (footprint "eagle-import:SIL7")
      (libsource (lib "eagle-import") (part "G06R"))
    )
  )
  (nets
    (net (code "3") (name "+3V3") (class "Default")
      (node (ref "C10") (pin "1") (pinfunction "1_1") (pintype "passive"))
      (node (ref "C8") (pin "+") (pinfunction "+_+") (pintype "passive"))
      (node (ref "IC2") (pin "3") (pinfunction "OUT_3") (pintype "passive"))
      (node (ref "IC3") (pin "1") (pinfunction "VDD_1") (pintype "power_in"))
      (node (ref "U$26") (pin "4") (pinfunction "VDD_4") (pintype "power_in"))
    )
    (net (code "4") (name "+5V") (class "Default")
      (node (ref "C11") (pin "1") (pinfunction "1_1") (pintype "passive"))
      (node (ref "C2") (pin "1") (pinfunction "1_1") (pintype "passive"))
      (node (ref "C20") (pin "1") (pinfunction "1_1") (pintype "passive"))
      (node (ref "C21") (pin "1") (pinfunction "1_1") (pintype "passive"))
      (node (ref "C23") (pin "+") (pinfunction "+_+") (pintype "passive"))
      (node (ref "C25") (pin "1") (pinfunction "1_1") (pintype "passive"))
      (node (ref "C26") (pin "1") (pinfunction "1_1") (pintype "passive"))
      (node (ref "C27") (pin "1") (pinfunction "1_1") (pintype "passive"))
      (node (ref "D8") (pin "A") (pinfunction "A_A") (pintype "passive"))
      (node (ref "D9") (pin "C") (pinfunction "C_C") (pintype "passive"))
      (node (ref "IC10") (pin "10") (pinfunction "SCL_10") (pintype "input"))
      (node (ref "IC10") (pin "16") (pinfunction "VCC_16") (pintype "power_in"))
      (node (ref "IC11") (pin "10") (pinfunction "SCL_10") (pintype "input"))
      (node (ref "IC11") (pin "16") (pinfunction "VCC_16") (pintype "power_in"))
      (node (ref "IC2") (pin "2") (pinfunction "IN_2") (pintype "input"))
      (node (ref "IC4") (pin "16") (pinfunction "VCC_16") (pintype "power_in"))
      (node (ref "IC4") (pin "6") (pinfunction "G1_6") (pintype "input"))
      (node (ref "IC7") (pin "OUT") (pinfunction "OUT_OUT") (pintype "passive"))
      (node (ref "IC8") (pin "10") (pinfunction "VCC_10") (pintype "power_in"))
      (node (ref "IC8") (pin "30") (pinfunction "AVCC_30") (pintype "power_in"))
      (node (ref "IC9") (pin "16") (pinfunction "VCC_16") (pintype "power_in"))
      (node (ref "JP1") (pin "6") (pinfunction "6_6") (pintype "passive"))
      (node (ref "JP3") (pin "6") (pinfunction "6_6") (pintype "passive"))
      (node (ref "JP5") (pin "6") (pinfunction "6_6") (pintype "passive"))
      (node (ref "JP7") (pin "6") (pinfunction "6_6") (pintype "passive"))
      (node (ref "OK1") (pin "8") (pinfunction "VCC_8") (pintype "passive"))
      (node (ref "R10") (pin "2") (pinfunction "2_2") (pintype "passive"))
      (node (ref "R15") (pin "1") (pinfunction "1_1") (pintype "passive"))
      (node (ref "R16") (pin "2") (pinfunction "2_2") (pintype "passive"))
      (node (ref "R28") (pin "P$1") (pinfunction "E_P$1") (pintype "passive"))
      (node (ref "R29") (pin "P$1") (pinfunction "E_P$1") (pintype "passive"))
      (node (ref "R30") (pin "P$1") (pinfunction "E_P$1") (pintype "passive"))
      (node (ref "R31") (pin "P$1") (pinfunction "E_P$1") (pintype "passive"))
      (node (ref "R36") (pin "1") (pinfunction "E_1") (pintype "passive"))
      (node (ref "R37") (pin "P$1") (pinfunction "E_P$1") (pintype "passive"))
      (node (ref "R38") (pin "P$1") (pinfunction "E_P$1") (pintype "passive"))
      (node (ref "R39") (pin "P$1") (pinfunction "E_P$1") (pintype "passive"))
      (node (ref "R40") (pin "P$1") (pinfunction "E_P$1") (pintype "passive"))
      (node (ref "R9") (pin "2") (pinfunction "2_2") (pintype "passive"))
      (node (ref "RN2") (pin "1") (pinfunction "1_1") (pintype "passive"))
      (node (ref "U$22") (pin "2") (pinfunction "VDD_2") (pintype "power_in"))
      (node (ref "U1") (pin "2") (pinfunction "2_2") (pintype "passive"))
    )
    (net (code "13") (name "AUDIO0") (class "Default")
      (node (ref "JP1") (pin "1") (pinfunction "1_1") (pintype "passive"))
      (node (ref "R2") (pin "1") (pinfunction "1_1") (pintype "passive"))
    )
    (net (code "14") (name "AUDIO1") (class "Default")
      (node (ref "JP1") (pin "2") (pinfunction "2_2") (pintype "passive"))
      (node (ref "R3") (pin "1") (pinfunction "1_1") (pintype "passive"))
    )
    (net (code "15") (name "AUDIO2") (class "Default")
      (node (ref "JP3") (pin "1") (pinfunction "1_1") (pintype "passive"))
      (node (ref "R4") (pin "1") (pinfunction "1_1") (pintype "passive"))
    )
    (net (code "16") (name "AUDIO3") (class "Default")
      (node (ref "JP3") (pin "2") (pinfunction "2_2") (pintype "passive"))
      (node (ref "R5") (pin "1") (pinfunction "1_1") (pintype "passive"))
    )
    (net (code "17") (name "AUDIO4") (class "Default")
      (node (ref "JP5") (pin "1") (pinfunction "1_1") (pintype "passive"))
      (node (ref "R6") (pin "1") (pinfunction "1_1") (pintype "passive"))
    )
    (net (code "18") (name "AUDIO5") (class "Default")
      (node (ref "JP5") (pin "2") (pinfunction "2_2") (pintype "passive"))
      (node (ref "R7") (pin "1") (pinfunction "1_1") (pintype "passive"))
    )
    (net (code "19") (name "ENC_A") (class "Default")
      (node (ref "IC8") (pin "24") (pinfunction "(TCK)PC2_24") (pintype "bidirectional"))
      (node (ref "SW1") (pin "A") (pinfunction "A_A") (pintype "passive"))
    )
    (net (code "20") (name "ENC_B") (class "Default")
      (node (ref "IC8") (pin "25") (pinfunction "(TMS)PC3_25") (pintype "bidirectional"))
      (node (ref "SW1") (pin "B") (pinfunction "B_B") (pintype "passive"))
    )
    (net (code "21") (name "ENC_CLICK") (class "Default")
      (node (ref "IC8") (pin "23") (pinfunction "(SDA)PC1_23") (pintype "bidirectional"))
      (node (ref "SW1") (pin "E") (pinfunction "2_E") (pintype "passive"))
    )
    (net (code "22") (name "GND") (class "Default")
      (node (ref "C1") (pin "2") (pinfunction "2_2") (pintype "passive"))
      (node (ref "C10") (pin "2") (pinfunction "2_2") (pintype "passive"))
      (node (ref "C11") (pin "2") (pinfunction "2_2") (pintype "passive"))
      (node (ref "C12") (pin "-") (pinfunction "-_-") (pintype "passive"))
      (node (ref "C13") (pin "1") (pinfunction "1_1") (pintype "passive"))
      (node (ref "C14") (pin "+") (pinfunction "+_+") (pintype "passive"))
      (node (ref "C15") (pin "2") (pinfunction "2_2") (pintype "passive"))
      (node (ref "C16") (pin "-") (pinfunction "-_-") (pintype "passive"))
      (node (ref "C17") (pin "2") (pinfunction "2_2") (pintype "passive"))
      (node (ref "C18") (pin "2") (pinfunction "2_2") (pintype "passive"))
      (node (ref "C19") (pin "2") (pinfunction "2_2") (pintype "passive"))
      (node (ref "C2") (pin "2") (pinfunction "2_2") (pintype "passive"))
      (node (ref "C20") (pin "2") (pinfunction "2_2") (pintype "passive"))
      (node (ref "C21") (pin "2") (pinfunction "2_2") (pintype "passive"))
      (node (ref "C22") (pin "1") (pinfunction "1_1") (pintype "passive"))
      (node (ref "C23") (pin "-") (pinfunction "-_-") (pintype "passive"))
      (node (ref "C24") (pin "1") (pinfunction "1_1") (pintype "passive"))
      (node (ref "C25") (pin "2") (pinfunction "2_2") (pintype "passive"))
      (node (ref "C26") (pin "2") (pinfunction "2_2") (pintype "passive"))
      (node (ref "C27") (pin "2") (pinfunction "2_2") (pintype "passive"))
      (node (ref "C3") (pin "2") (pinfunction "2_2") (pintype "passive"))
      (node (ref "C4") (pin "+") (pinfunction "+_+") (pintype "passive"))
      (node (ref "C7") (pin "1") (pinfunction "1_1") (pintype "passive"))
      (node (ref "C8") (pin "-") (pinfunction "-_-") (pintype "passive"))
      (node (ref "C9") (pin "-") (pinfunction "-_-") (pintype "passive"))
      (node (ref "D5") (pin "C") (pinfunction "C_C") (pintype "passive"))
      (node (ref "D7") (pin "A") (pinfunction "A_A") (pintype "passive"))
      (node (ref "D9") (pin "A") (pinfunction "A_A") (pintype "passive"))
      (node (ref "IC1") (pin "3") (pinfunction "+IN_3") (pintype "input"))
      (node (ref "IC1") (pin "5") (pinfunction "+IN_5") (pintype "input"))
      (node (ref "IC10") (pin "13") (pinfunction "G_13") (pintype "input"))
      (node (ref "IC10") (pin "8") (pinfunction "GND_8") (pintype "power_in"))
      (node (ref "IC11") (pin "13") (pinfunction "G_13") (pintype "input"))
      (node (ref "IC11") (pin "8") (pinfunction "GND_8") (pintype "power_in"))
      (node (ref "IC2") (pin "1") (pinfunction "GND_1") (pintype "input"))
      (node (ref "IC3") (pin "11") (pinfunction "I_11") (pintype "input"))
      (node (ref "IC3") (pin "14") (pinfunction "I_14") (pintype "input"))
      (node (ref "IC3") (pin "8") (pinfunction "VSS_8") (pintype "power_in"))
      (node (ref "IC3") (pin "9") (pinfunction "I_9") (pintype "input"))
      (node (ref "IC4") (pin "5") (pinfunction "G2B_5") (pintype "input"))
      (node (ref "IC4") (pin "8") (pinfunction "GND_8") (pintype "power_in"))
      (node (ref "IC5") (pin "GND") (pinfunction "GND_GND") (pintype "input"))
      (node (ref "IC6") (pin "GND") (pinfunction "GND_GND") (pintype "input"))
      (node (ref "IC7") (pin "GND") (pinfunction "GND_GND") (pintype "input"))
      (node (ref "IC8") (pin "11") (pinfunction "GND_11") (pintype "power_in"))
      (node (ref "IC8") (pin "31") (pinfunction "GND_31") (pintype "power_in"))
      (node (ref "IC9") (pin "10") (pinfunction "SER_10") (pintype "input"))
      (node (ref "IC9") (pin "15") (pinfunction "INH_15") (pintype "input"))
      (node (ref "IC9") (pin "8") (pinfunction "GND_8") (pintype "power_in"))
      (node (ref "J1") (pin "1") (pinfunction "1_1") (pintype "passive"))
      (node (ref "J2") (pin "S") (pinfunction "S_S") (pintype "passive"))
      (node (ref "J2") (pin "SN") (pinfunction "SN_SN") (pintype "passive"))
      (node (ref "J3") (pin "S") (pinfunction "S_S") (pintype "passive"))
      (node (ref "J3") (pin "SN") (pinfunction "SN_SN") (pintype "passive"))
      (node (ref "J4") (pin "S") (pinfunction "S_S") (pintype "passive"))
      (node (ref "J4") (pin "SN") (pinfunction "SN_SN") (pintype "passive"))
      (node (ref "J5") (pin "S") (pinfunction "S_S") (pintype "passive"))
      (node (ref "J5") (pin "SN") (pinfunction "SN_SN") (pintype "passive"))
      (node (ref "J6") (pin "S") (pinfunction "S_S") (pintype "passive"))
      (node (ref "J6") (pin "SN") (pinfunction "SN_SN") (pintype "passive"))
      (node (ref "J7") (pin "S") (pinfunction "S_S") (pintype "passive"))
      (node (ref "J7") (pin "SN") (pinfunction "SN_SN") (pintype "passive"))
      (node (ref "J8") (pin "S") (pinfunction "S_S") (pintype "passive"))
      (node (ref "J8") (pin "SN") (pinfunction "SN_SN") (pintype "passive"))
      (node (ref "JP1") (pin "4") (pinfunction "4_4") (pintype "passive"))
      (node (ref "JP2") (pin "6") (pinfunction "6_6") (pintype "passive"))
      (node (ref "JP3") (pin "4") (pinfunction "4_4") (pintype "passive"))
      (node (ref "JP4") (pin "6") (pinfunction "6_6") (pintype "passive"))
      (node (ref "JP5") (pin "4") (pinfunction "4_4") (pintype "passive"))
      (node (ref "JP6") (pin "6") (pinfunction "6_6") (pintype "passive"))
      (node (ref "JP7") (pin "5") (pinfunction "5_5") (pintype "passive"))
      (node (ref "OK1") (pin "5") (pinfunction "GND_5") (pintype "passive"))
      (node (ref "R28") (pin "P$3") (pinfunction "A_P$3") (pintype "passive"))
      (node (ref "R29") (pin "P$3") (pinfunction "A_P$3") (pintype "passive"))
      (node (ref "R30") (pin "P$3") (pinfunction "A_P$3") (pintype "passive"))
      (node (ref "R31") (pin "P$3") (pinfunction "A_P$3") (pintype "passive"))
      (node (ref "R36") (pin "3") (pinfunction "A_3") (pintype "passive"))
      (node (ref "R37") (pin "P$3") (pinfunction "A_P$3") (pintype "passive"))
      (node (ref "R38") (pin "P$3") (pinfunction "A_P$3") (pintype "passive"))
      (node (ref "R39") (pin "P$3") (pinfunction "A_P$3") (pintype "passive"))
      (node (ref "R40") (pin "P$3") (pinfunction "A_P$3") (pintype "passive"))
      (node (ref "R41") (pin "P$3") (pinfunction "A_P$3") (pintype "passive"))
      (node (ref "S1") (pin "1") (pinfunction "S_1") (pintype "passive"))
      (node (ref "S1") (pin "2") (pinfunction "S1_2") (pintype "passive"))
      (node (ref "S2") (pin "1") (pinfunction "S_1") (pintype "passive"))
      (node (ref "S2") (pin "2") (pinfunction "S1_2") (pintype "passive"))
      (node (ref "S3") (pin "1") (pinfunction "S_1") (pintype "passive"))
      (node (ref "S3") (pin "2") (pinfunction "S1_2") (pintype "passive"))
      (node (ref "S4") (pin "1") (pinfunction "S_1") (pintype "passive"))
      (node (ref "S4") (pin "2") (pinfunction "S1_2") (pintype "passive"))
      (node (ref "S5") (pin "1") (pinfunction "S_1") (pintype "passive"))
      (node (ref "S5") (pin "2") (pinfunction "S1_2") (pintype "passive"))
      (node (ref "S6") (pin "1") (pinfunction "S_1") (pintype "passive"))
      (node (ref "S6") (pin "2") (pinfunction "S1_2") (pintype "passive"))
      (node (ref "S7") (pin "1") (pinfunction "S_1") (pintype "passive"))
      (node (ref "S7") (pin "2") (pinfunction "S1_2") (pintype "passive"))
      (node (ref "S8") (pin "1") (pinfunction "S_1") (pintype "passive"))
      (node (ref "S8") (pin "2") (pinfunction "S1_2") (pintype "passive"))
      (node (ref "SW1") (pin "C") (pinfunction "C_C") (pintype "passive"))
      (node (ref "SW1") (pin "D") (pinfunction "1_D") (pintype "passive"))
      (node (ref "U$22") (pin "1") (pinfunction "VSS_1") (pintype "power_in"))
      (node (ref "U$22") (pin "16") (pinfunction "K_16") (pintype "power_in"))
      (node (ref "U$22") (pin "5") (pinfunction "R/W_5") (pintype "input"))
      (node (ref "U$26") (pin "3") (pinfunction "VSS1_3") (pintype "power_in"))
      (node (ref "U$26") (pin "6") (pinfunction "VSS2_6") (pintype "power_in"))
      (node (ref "U$26") (pin "GP") (pinfunction "GND_GP") (pintype "power_in"))
      (node (ref "U$26") (pin "GP3") (pinfunction "COMMON_SW_GP3") (pintype "passive"))
      (node (ref "U1") (pin "6") (pinfunction "6_6") (pintype "passive"))
      (node (ref "X2") (pin "2") (pinfunction "2_2") (pintype "passive"))
    )
    (net (code "23") (name "IO_ENABLE") (class "Default")
      (node (ref "IC10") (pin "12") (pinfunction "RCK_12") (pintype "input"))
      (node (ref "IC11") (pin "12") (pinfunction "RCK_12") (pintype "input"))
      (node (ref "IC8") (pin "26") (pinfunction "(TDO)PC4_26") (pintype "bidirectional"))
      (node (ref "IC9") (pin "1") (pinfunction "SH/~{LD}_1") (pintype "input"))
    )
    (net (code "24") (name "IO_INPUT") (class "Default")
      (node (ref "IC8") (pin "28") (pinfunction "(TOSC1)PC6_28") (pintype "bidirectional"))
      (node (ref "IC9") (pin "9") (pinfunction "QH_9") (pintype "output"))
    )
    (net (code "25") (name "IO_OUTPUT") (class "Default")
      (node (ref "IC11") (pin "14") (pinfunction "SER_14") (pintype "input"))
      (node (ref "IC8") (pin "27") (pinfunction "(TDI)PC5_27") (pintype "bidirectional"))
    )
    (net (code "26") (name "IO_SCK") (class "Default")
      (node (ref "IC10") (pin "11") (pinfunction "SCK_11") (pintype "input"))
      (node (ref "IC11") (pin "11") (pinfunction "SCK_11") (pintype "input"))
      (node (ref "IC8") (pin "29") (pinfunction "(TOSC2)PC7_29") (pintype "bidirectional"))
      (node (ref "IC9") (pin "2") (pinfunction "CLK_2") (pintype "input"))
    )
    (net (code "27") (name "LCD_DATA4") (class "Default")
      (node (ref "IC8") (pin "18") (pinfunction "(OC1B)PD4_18") (pintype "bidirectional"))
      (node (ref "U$22") (pin "11") (pinfunction "DB4_11") (pintype "bidirectional"))
    )
    (net (code "28") (name "LCD_DATA5") (class "Default")
      (node (ref "IC8") (pin "19") (pinfunction "(OC1A)PD5_19") (pintype "bidirectional"))
      (node (ref "U$22") (pin "12") (pinfunction "DB5_12") (pintype "bidirectional"))
    )
    (net (code "29") (name "LCD_DATA6") (class "Default")
      (node (ref "IC8") (pin "20") (pinfunction "(ICP)PD6_20") (pintype "bidirectional"))
      (node (ref "U$22") (pin "13") (pinfunction "DB6_13") (pintype "bidirectional"))
    )
    (net (code "30") (name "LCD_DATA7") (class "Default")
      (node (ref "IC8") (pin "21") (pinfunction "(OC2)PD7_21") (pintype "bidirectional"))
      (node (ref "U$22") (pin "14") (pinfunction "DB7_14") (pintype "bidirectional"))
    )
    (net (code "31") (name "LCD_ENABLE") (class "Default")
      (node (ref "IC8") (pin "16") (pinfunction "(INT0)PD2_16") (pintype "bidirectional"))
      (node (ref "U$22") (pin "6") (pinfunction "E_6") (pintype "input"))
    )
    (net (code "32") (name "LCD_RS") (class "Default")
      (node (ref "IC8") (pin "17") (pinfunction "(INT1)PD3_17") (pintype "bidirectional"))
      (node (ref "U$22") (pin "4") (pinfunction "RS_4") (pintype "input"))
    )
    (net (code "33") (name "MIDI_IN") (class "Default")
      (node (ref "IC8") (pin "14") (pinfunction "(RXD)PD0_14") (pintype "bidirectional"))
      (node (ref "OK1") (pin "6") (pinfunction "VO_6") (pintype "passive"))
      (node (ref "R9") (pin "1") (pinfunction "1_1") (pintype "passive"))
    )
    (net (code "34") (name "MIDI_OUT") (class "Default")
      (node (ref "IC8") (pin "15") (pinfunction "(TXD)PD1_15") (pintype "bidirectional"))
      (node (ref "R11") (pin "1") (pinfunction "1_1") (pintype "passive"))
    )
    (net (code "35") (name "MISO") (class "Default")
      (node (ref "IC8") (pin "7") (pinfunction "(MISO)PB6_7") (pintype "bidirectional"))
      (node (ref "JP2") (pin "4") (pinfunction "4_4") (pintype "passive"))
      (node (ref "JP4") (pin "4") (pinfunction "4_4") (pintype "passive"))
      (node (ref "JP6") (pin "4") (pinfunction "4_4") (pintype "passive"))
      (node (ref "JP7") (pin "2") (pinfunction "2_2") (pintype "passive"))
      (node (ref "U$26") (pin "7") (pinfunction "DATA_OUT_7") (pintype "output"))
      (node (ref "U1") (pin "1") (pinfunction "1_1") (pintype "passive"))
    )
    (net (code "36") (name "MOSI") (class "Default")
      (node (ref "IC3") (pin "3") (pinfunction "I_3") (pintype "input"))
      (node (ref "IC8") (pin "6") (pinfunction "(MOSI)PB5_6") (pintype "bidirectional"))
      (node (ref "JP2") (pin "3") (pinfunction "3_3") (pintype "passive"))
      (node (ref "JP4") (pin "3") (pinfunction "3_3") (pintype "passive"))
      (node (ref "JP6") (pin "3") (pinfunction "3_3") (pintype "passive"))
      (node (ref "JP7") (pin "3") (pinfunction "3_3") (pintype "passive"))
      (node (ref "U1") (pin "4") (pinfunction "4_4") (pintype "passive"))
    )
    (net (code "37") (name "Net-(C1-Pad1)") (class "Default")
      (node (ref "C1") (pin "1") (pinfunction "1_1") (pintype "passive"))
      (node (ref "D1") (pin "C") (pinfunction "C_C") (pintype "passive"))
      (node (ref "D2") (pin "A") (pinfunction "A_A") (pintype "passive"))
      (node (ref "SW") (pin "2") (pinfunction "2_2") (pintype "passive"))
    )
    (net (code "38") (name "Net-(C5-Pad2)") (class "Default")
      (node (ref "C5") (pin "2") (pinfunction "2_2") (pintype "passive"))
      (node (ref "J2") (pin "T") (pinfunction "T_T") (pintype "passive"))
      (node (ref "R1") (pin "2") (pinfunction "2_2") (pintype "passive"))
      (node (ref "R12") (pin "2") (pinfunction "2_2") (pintype "passive"))
    )
    (net (code "39") (name "Net-(C12-Pad+)") (class "Default")
      (node (ref "C12") (pin "+") (pinfunction "+_+") (pintype "passive"))
      (node (ref "C15") (pin "1") (pinfunction "1_1") (pintype "passive"))
      (node (ref "C18") (pin "1") (pinfunction "1_1") (pintype "passive"))
      (node (ref "C9") (pin "+") (pinfunction "+_+") (pintype "passive"))
      (node (ref "D2") (pin "C") (pinfunction "C_C") (pintype "passive"))
      (node (ref "D6") (pin "C") (pinfunction "C_C") (pintype "passive"))
      (node (ref "D8") (pin "C") (pinfunction "C_C") (pintype "passive"))
      (node (ref "IC6") (pin "IN") (pinfunction "IN_IN") (pintype "input"))
      (node (ref "IC7") (pin "IN") (pinfunction "IN_IN") (pintype "input"))
    )
    (net (code "40") (name "Net-(C13-Pad2)") (class "Default")
      (node (ref "C13") (pin "2") (pinfunction "2_2") (pintype "passive"))
      (node (ref "C4") (pin "-") (pinfunction "-_-") (pintype "passive"))
      (node (ref "D1") (pin "A") (pinfunction "A_A") (pintype "passive"))
      (node (ref "D4") (pin "A") (pinfunction "A_A") (pintype "passive"))
      (node (ref "IC5") (pin "IN") (pinfunction "IN_IN") (pintype "input"))
    )
    (net (code "41") (name "Net-(IC1A--IN)") (class "Default")
      (node (ref "C5") (pin "1") (pinfunction "1_1") (pintype "passive"))
      (node (ref "IC1") (pin "2") (pinfunction "-IN_2") (pintype "input"))
      (node (ref "R12") (pin "1") (pinfunction "1_1") (pintype "passive"))
      (node (ref "R14") (pin "2") (pinfunction "2_2") (pintype "passive"))
    )
    (net (code "42") (name "Net-(IC1A-OUT)") (class "Default")
      (node (ref "IC1") (pin "1") (pinfunction "OUT_1") (pintype "output"))
      (node (ref "R1") (pin "1") (pinfunction "1_1") (pintype "passive"))
    )
    (net (code "43") (name "Net-(IC1B--IN)") (class "Default")
      (node (ref "C6") (pin "1") (pinfunction "1_1") (pintype "passive"))
      (node (ref "IC1") (pin "6") (pinfunction "-IN_6") (pintype "input"))
      (node (ref "R13") (pin "1") (pinfunction "1_1") (pintype "passive"))
      (node (ref "RN1") (pin "1") (pinfunction "1_1") (pintype "passive"))
    )
    (net (code "44") (name "Net-(IC1B-OUT)") (class "Default")
      (node (ref "C6") (pin "2") (pinfunction "2_2") (pintype "passive"))
      (node (ref "IC1") (pin "7") (pinfunction "OUT_7") (pintype "output"))
      (node (ref "R13") (pin "2") (pinfunction "2_2") (pintype "passive"))
      (node (ref "R41") (pin "P$1") (pinfunction "E_P$1") (pintype "passive"))
    )
    (net (code "45") (name "Net-(IC3A-O)") (class "Default")
      (node (ref "IC3") (pin "2") (pinfunction "O_2") (pintype "output"))
      (node (ref "U$26") (pin "2") (pinfunction "DATA_IN_2") (pintype "input"))
    )
    (net (code "46") (name "Net-(IC3B-O)") (class "Default")
      (node (ref "IC3") (pin "4") (pinfunction "O_4") (pintype "output"))
      (node (ref "U$26") (pin "5") (pinfunction "SCLK_5") (pintype "input"))
    )
    (net (code "47") (name "Net-(IC3C-O)") (class "Default")
      (node (ref "IC3") (pin "6") (pinfunction "O_6") (pintype "output"))
      (node (ref "U$26") (pin "1") (pinfunction "CS_1") (pintype "input"))
    )
    (net (code "48") (name "Net-(IC8-AREF)") (class "Default")
      (node (ref "C19") (pin "1") (pinfunction "1_1") (pintype "passive"))
      (node (ref "IC8") (pin "32") (pinfunction "AREF_32") (pintype "passive"))
    )
    (net (code "49") (name "Net-(IC8-XTAL1)") (class "Default")
      (node (ref "C24") (pin "2") (pinfunction "2_2") (pintype "passive"))
      (node (ref "IC8") (pin "13") (pinfunction "XTAL1_13") (pintype "bidirectional"))
      (node (ref "Q1") (pin "1") (pinfunction "1_1") (pintype "passive"))
    )
    (net (code "50") (name "Net-(IC8-XTAL2)") (class "Default")
      (node (ref "C22") (pin "2") (pinfunction "2_2") (pintype "passive"))
      (node (ref "IC8") (pin "12") (pinfunction "XTAL2_12") (pintype "bidirectional"))
      (node (ref "Q1") (pin "2") (pinfunction "2_2") (pintype "passive"))
    )
    (net (code "51") (name "Net-(IC9A-A)") (class "Default")
      (node (ref "IC9") (pin "11") (pinfunction "A_11") (pintype "input"))
      (node (ref "RN2") (pin "9") (pinfunction "9_9") (pintype "passive"))
      (node (ref "S1") (pin "3") (pinfunction "P_3") (pintype "passive"))
      (node (ref "S1") (pin "4") (pinfunction "P1_4") (pintype "passive"))
    )
    (net (code "52") (name "Net-(IC9A-B)") (class "Default")
      (node (ref "IC9") (pin "12") (pinfunction "B_12") (pintype "input"))
      (node (ref "RN2") (pin "8") (pinfunction "8_8") (pintype "passive"))
      (node (ref "S2") (pin "3") (pinfunction "P_3") (pintype "passive"))
      (node (ref "S2") (pin "4") (pinfunction "P1_4") (pintype "passive"))
    )
    (net (code "53") (name "Net-(IC9A-C)") (class "Default")
      (node (ref "IC9") (pin "13") (pinfunction "C_13") (pintype "input"))
      (node (ref "RN2") (pin "7") (pinfunction "7_7") (pintype "passive"))
      (node (ref "S3") (pin "3") (pinfunction "P_3") (pintype "passive"))
      (node (ref "S3") (pin "4") (pinfunction "P1_4") (pintype "passive"))
    )
    (net (code "54") (name "Net-(IC9A-D)") (class "Default")
      (node (ref "IC9") (pin "14") (pinfunction "D_14") (pintype "input"))
      (node (ref "RN2") (pin "6") (pinfunction "6_6") (pintype "passive"))
      (node (ref "S4") (pin "3") (pinfunction "P_3") (pintype "passive"))
      (node (ref "S4") (pin "4") (pinfunction "P1_4") (pintype "passive"))
    )
    (net (code "55") (name "Net-(IC9A-E)") (class "Default")
      (node (ref "IC9") (pin "3") (pinfunction "E_3") (pintype "input"))
      (node (ref "RN2") (pin "5") (pinfunction "5_5") (pintype "passive"))
      (node (ref "S5") (pin "3") (pinfunction "P_3") (pintype "passive"))
      (node (ref "S5") (pin "4") (pinfunction "P1_4") (pintype "passive"))
    )
    (net (code "56") (name "Net-(IC9A-F)") (class "Default")
      (node (ref "IC9") (pin "4") (pinfunction "F_4") (pintype "input"))
      (node (ref "RN2") (pin "4") (pinfunction "4_4") (pintype "passive"))
      (node (ref "S6") (pin "3") (pinfunction "P_3") (pintype "passive"))
      (node (ref "S6") (pin "4") (pinfunction "P1_4") (pintype "passive"))
    )
    (net (code "57") (name "Net-(IC9A-G)") (class "Default")
      (node (ref "IC9") (pin "5") (pinfunction "G_5") (pintype "input"))
      (node (ref "RN2") (pin "3") (pinfunction "3_3") (pintype "passive"))
      (node (ref "S7") (pin "3") (pinfunction "P_3") (pintype "passive"))
      (node (ref "S7") (pin "4") (pinfunction "P1_4") (pintype "passive"))
    )
    (net (code "58") (name "Net-(IC9A-H)") (class "Default")
      (node (ref "IC9") (pin "6") (pinfunction "H_6") (pintype "input"))
      (node (ref "RN2") (pin "2") (pinfunction "2_2") (pintype "passive"))
      (node (ref "S8") (pin "3") (pinfunction "P_3") (pintype "passive"))
      (node (ref "S8") (pin "4") (pinfunction "P1_4") (pintype "passive"))
    )
    (net (code "59") (name "Net-(IC10A-QA)") (class "Default")
      (node (ref "IC10") (pin "15") (pinfunction "QA_15") (pintype "tri_state"))
      (node (ref "R34") (pin "1") (pinfunction "1_1") (pintype "passive"))
    )
    (net (code "60") (name "Net-(IC10A-QB)") (class "Default")
      (node (ref "IC10") (pin "1") (pinfunction "QB_1") (pintype "tri_state"))
      (node (ref "R32") (pin "1") (pinfunction "1_1") (pintype "passive"))
    )
    (net (code "61") (name "Net-(IC10A-QC)") (class "Default")
      (node (ref "IC10") (pin "2") (pinfunction "QC_2") (pintype "tri_state"))
      (node (ref "R26") (pin "1") (pinfunction "1_1") (pintype "passive"))
    )
    (net (code "62") (name "Net-(IC10A-QD)") (class "Default")
      (node (ref "IC10") (pin "3") (pinfunction "QD_3") (pintype "tri_state"))
      (node (ref "R24") (pin "1") (pinfunction "1_1") (pintype "passive"))
    )
    (net (code "63") (name "Net-(IC10A-QE)") (class "Default")
      (node (ref "IC10") (pin "4") (pinfunction "QE_4") (pintype "tri_state"))
      (node (ref "R22") (pin "1") (pinfunction "1_1") (pintype "passive"))
    )
    (net (code "64") (name "Net-(IC10A-QF)") (class "Default")
      (node (ref "IC10") (pin "5") (pinfunction "QF_5") (pintype "tri_state"))
      (node (ref "R20") (pin "1") (pinfunction "1_1") (pintype "passive"))
    )
    (net (code "65") (name "Net-(IC10A-QG)") (class "Default")
      (node (ref "IC10") (pin "6") (pinfunction "QG_6") (pintype "tri_state"))
      (node (ref "R18") (pin "1") (pinfunction "1_1") (pintype "passive"))
    )
    (net (code "66") (name "Net-(IC10A-QH)") (class "Default")
      (node (ref "IC10") (pin "7") (pinfunction "QH_7") (pintype "tri_state"))
      (node (ref "LED1") (pin "K") (pinfunction "C_K") (pintype "passive"))
      (node (ref "LED10") (pin "K") (pinfunction "C_K") (pintype "passive"))
      (node (ref "LED11") (pin "K") (pinfunction "C_K") (pintype "passive"))
      (node (ref "LED12") (pin "K") (pinfunction "C_K") (pintype "passive"))
      (node (ref "LED13") (pin "K") (pinfunction "C_K") (pintype "passive"))
      (node (ref "LED14") (pin "K") (pinfunction "C_K") (pintype "passive"))
      (node (ref "LED15") (pin "K") (pinfunction "C_K") (pintype "passive"))
      (node (ref "LED2") (pin "K") (pinfunction "C_K") (pintype "passive"))
      (node (ref "LED3") (pin "K") (pinfunction "C_K") (pintype "passive"))
      (node (ref "LED4") (pin "K") (pinfunction "C_K") (pintype "passive"))
      (node (ref "LED5") (pin "K") (pinfunction "C_K") (pintype "passive"))
      (node (ref "LED6") (pin "K") (pinfunction "C_K") (pintype "passive"))
      (node (ref "LED7") (pin "K") (pinfunction "C_K") (pintype "passive"))
      (node (ref "LED8") (pin "K") (pinfunction "C_K") (pintype "passive"))
      (node (ref "LED9") (pin "K") (pinfunction "C_K") (pintype "passive"))
    )
    (net (code "67") (name "Net-(IC10A-SER)") (class "Default")
      (node (ref "IC10") (pin "14") (pinfunction "SER_14") (pintype "input"))
      (node (ref "IC11") (pin "9") (pinfunction "QH*_9") (pintype "tri_state"))
    )
    (net (code "68") (name "Net-(IC11A-QA)") (class "Default")
      (node (ref "IC11") (pin "15") (pinfunction "QA_15") (pintype "tri_state"))
      (node (ref "R35") (pin "1") (pinfunction "1_1") (pintype "passive"))
    )
    (net (code "69") (name "Net-(IC11A-QB)") (class "Default")
      (node (ref "IC11") (pin "1") (pinfunction "QB_1") (pintype "tri_state"))
      (node (ref "R33") (pin "1") (pinfunction "1_1") (pintype "passive"))
    )
    (net (code "70") (name "Net-(IC11A-QC)") (class "Default")
      (node (ref "IC11") (pin "2") (pinfunction "QC_2") (pintype "tri_state"))
      (node (ref "R27") (pin "1") (pinfunction "1_1") (pintype "passive"))
    )
    (net (code "71") (name "Net-(IC11A-QD)") (class "Default")
      (node (ref "IC11") (pin "3") (pinfunction "QD_3") (pintype "tri_state"))
      (node (ref "R25") (pin "1") (pinfunction "1_1") (pintype "passive"))
    )
    (net (code "72") (name "Net-(IC11A-QE)") (class "Default")
      (node (ref "IC11") (pin "4") (pinfunction "QE_4") (pintype "tri_state"))
      (node (ref "R23") (pin "1") (pinfunction "1_1") (pintype "passive"))
    )
    (net (code "73") (name "Net-(IC11A-QF)") (class "Default")
      (node (ref "IC11") (pin "5") (pinfunction "QF_5") (pintype "tri_state"))
      (node (ref "R21") (pin "1") (pinfunction "1_1") (pintype "passive"))
    )
    (net (code "74") (name "Net-(IC11A-QG)") (class "Default")
      (node (ref "IC11") (pin "6") (pinfunction "QG_6") (pintype "tri_state"))
      (node (ref "R19") (pin "1") (pinfunction "1_1") (pintype "passive"))
    )
    (net (code "75") (name "Net-(IC11A-QH)") (class "Default")
      (node (ref "IC11") (pin "7") (pinfunction "QH_7") (pintype "tri_state"))
      (node (ref "R17") (pin "1") (pinfunction "1_1") (pintype "passive"))
    )
    (net (code "76") (name "Net-(J1-Pad3)") (class "Default")
      (node (ref "J1") (pin "3") (pinfunction "3_3") (pintype "passive"))
      (node (ref "SW") (pin "1") (pinfunction "1_1") (pintype "passive"))
    )
    (net (code "77") (name "Net-(J3-PadT)") (class "Default")
      (node (ref "J3") (pin "T") (pinfunction "T_T") (pintype "passive"))
      (node (ref "R2") (pin "2") (pinfunction "2_2") (pintype "passive"))
    )
    (net (code "78") (name "Net-(J4-PadT)") (class "Default")
      (node (ref "J4") (pin "T") (pinfunction "T_T") (pintype "passive"))
      (node (ref "R3") (pin "2") (pinfunction "2_2") (pintype "passive"))
    )
    (net (code "79") (name "Net-(J5-PadT)") (class "Default")
      (node (ref "J5") (pin "T") (pinfunction "T_T") (pintype "passive"))
      (node (ref "R4") (pin "2") (pinfunction "2_2") (pintype "passive"))
    )
    (net (code "80") (name "Net-(J6-PadT)") (class "Default")
      (node (ref "J6") (pin "T") (pinfunction "T_T") (pintype "passive"))
      (node (ref "R5") (pin "2") (pinfunction "2_2") (pintype "passive"))
    )
    (net (code "81") (name "Net-(J7-PadT)") (class "Default")
      (node (ref "J7") (pin "T") (pinfunction "T_T") (pintype "passive"))
      (node (ref "R6") (pin "2") (pinfunction "2_2") (pintype "passive"))
    )
    (net (code "82") (name "Net-(J8-PadT)") (class "Default")
      (node (ref "J8") (pin "T") (pinfunction "T_T") (pintype "passive"))
      (node (ref "R7") (pin "2") (pinfunction "2_2") (pintype "passive"))
    )
    (net (code "83") (name "Net-(LED1-PadA)") (class "Default")
      (node (ref "LED1") (pin "A") (pinfunction "A_A") (pintype "passive"))
      (node (ref "R26") (pin "2") (pinfunction "2_2") (pintype "passive"))
    )
    (net (code "84") (name "Net-(LED2-PadA)") (class "Default")
      (node (ref "LED2") (pin "A") (pinfunction "A_A") (pintype "passive"))
      (node (ref "R20") (pin "2") (pinfunction "2_2") (pintype "passive"))
    )
    (net (code "85") (name "Net-(LED3-PadA)") (class "Default")
      (node (ref "LED3") (pin "A") (pinfunction "A_A") (pintype "passive"))
      (node (ref "R32") (pin "2") (pinfunction "2_2") (pintype "passive"))
    )
    (net (code "86") (name "Net-(LED4-PadA)") (class "Default")
      (node (ref "LED4") (pin "A") (pinfunction "A_A") (pintype "passive"))
      (node (ref "R22") (pin "2") (pinfunction "2_2") (pintype "passive"))
    )
    (net (code "87") (name "Net-(LED5-PadA)") (class "Default")
      (node (ref "LED5") (pin "A") (pinfunction "A_A") (pintype "passive"))
      (node (ref "R34") (pin "2") (pinfunction "2_2") (pintype "passive"))
    )
    (net (code "88") (name "Net-(LED6-PadA)") (class "Default")
      (node (ref "LED6") (pin "A") (pinfunction "A_A") (pintype "passive"))
      (node (ref "R24") (pin "2") (pinfunction "2_2") (pintype "passive"))
    )
    (net (code "89") (name "Net-(LED7-PadA)") (class "Default")
      (node (ref "LED7") (pin "A") (pinfunction "A_A") (pintype "passive"))
      (node (ref "R18") (pin "2") (pinfunction "2_2") (pintype "passive"))
    )
    (net (code "90") (name "Net-(LED8-PadA)") (class "Default")
      (node (ref "LED8") (pin "A") (pinfunction "A_A") (pintype "passive"))
      (node (ref "R35") (pin "2") (pinfunction "2_2") (pintype "passive"))
    )
    (net (code "91") (name "Net-(LED9-PadA)") (class "Default")
      (node (ref "LED9") (pin "A") (pinfunction "A_A") (pintype "passive"))
      (node (ref "R33") (pin "2") (pinfunction "2_2") (pintype "passive"))
    )
    (net (code "92") (name "Net-(LED10-PadA)") (class "Default")
      (node (ref "LED10") (pin "A") (pinfunction "A_A") (pintype "passive"))
      (node (ref "R27") (pin "2") (pinfunction "2_2") (pintype "passive"))
    )
    (net (code "93") (name "Net-(LED11-PadA)") (class "Default")
      (node (ref "LED11") (pin "A") (pinfunction "A_A") (pintype "passive"))
      (node (ref "R25") (pin "2") (pinfunction "2_2") (pintype "passive"))
    )
    (net (code "94") (name "Net-(LED12-PadA)") (class "Default")
      (node (ref "LED12") (pin "A") (pinfunction "A_A") (pintype "passive"))
      (node (ref "R23") (pin "2") (pinfunction "2_2") (pintype "passive"))
    )
    (net (code "95") (name "Net-(LED13-PadA)") (class "Default")
      (node (ref "LED13") (pin "A") (pinfunction "A_A") (pintype "passive"))
      (node (ref "R21") (pin "2") (pinfunction "2_2") (pintype "passive"))
    )
    (net (code "96") (name "Net-(LED14-PadA)") (class "Default")
      (node (ref "LED14") (pin "A") (pinfunction "A_A") (pintype "passive"))
      (node (ref "R19") (pin "2") (pinfunction "2_2") (pintype "passive"))
    )
    (net (code "97") (name "Net-(LED15-PadA)") (class "Default")
      (node (ref "LED15") (pin "A") (pinfunction "A_A") (pintype "passive"))
      (node (ref "R17") (pin "2") (pinfunction "2_2") (pintype "passive"))
    )
    (net (code "98") (name "Net-(OK1-A)") (class "Default")
      (node (ref "D3") (pin "C") (pinfunction "C_C") (pintype "passive"))
      (node (ref "OK1") (pin "2") (pinfunction "A_2") (pintype "passive"))
      (node (ref "R8") (pin "2") (pinfunction "2_2") (pintype "passive"))
    )
    (net (code "99") (name "Net-(OK1-C)") (class "Default")
      (node (ref "D3") (pin "A") (pinfunction "A_A") (pintype "passive"))
      (node (ref "OK1") (pin "3") (pinfunction "C_3") (pintype "passive"))
      (node (ref "X1") (pin "5") (pinfunction "5_5") (pintype "passive"))
    )
    (net (code "100") (name "Net-(R8-Pad1)") (class "Default")
      (node (ref "R8") (pin "1") (pinfunction "1_1") (pintype "passive"))
      (node (ref "X1") (pin "4") (pinfunction "4_4") (pintype "passive"))
    )
    (net (code "101") (name "Net-(R10-Pad1)") (class "Default")
      (node (ref "R10") (pin "1") (pinfunction "1_1") (pintype "passive"))
      (node (ref "X2") (pin "4") (pinfunction "4_4") (pintype "passive"))
    )
    (net (code "102") (name "Net-(R11-Pad2)") (class "Default")
      (node (ref "R11") (pin "2") (pinfunction "2_2") (pintype "passive"))
      (node (ref "X2") (pin "5") (pinfunction "5_5") (pintype "passive"))
    )
    (net (code "103") (name "Net-(R36-S)") (class "Default")
      (node (ref "R36") (pin "2") (pinfunction "S_2") (pintype "passive"))
      (node (ref "U$22") (pin "3") (pinfunction "VO_3") (pintype "bidirectional"))
    )
    (net (code "104") (name "Net-(R41-S)") (class "Default")
      (node (ref "R14") (pin "1") (pinfunction "1_1") (pintype "passive"))
      (node (ref "R41") (pin "P$2") (pinfunction "S_P$2") (pintype "passive"))
    )
    (net (code "105") (name "Net-(U$22-A)") (class "Default")
      (node (ref "R15") (pin "2") (pinfunction "2_2") (pintype "passive"))
      (node (ref "U$22") (pin "15") (pinfunction "A_15") (pintype "power_in"))
    )
    (net (code "106") (name "POTS0") (class "Default")
      (node (ref "IC8") (pin "40") (pinfunction "(ADC0)PA0_40") (pintype "bidirectional"))
      (node (ref "R40") (pin "P$2") (pinfunction "S_P$2") (pintype "passive"))
    )
    (net (code "107") (name "POTS1") (class "Default")
      (node (ref "IC8") (pin "39") (pinfunction "(ADC1)PA1_39") (pintype "bidirectional"))
      (node (ref "R39") (pin "P$2") (pinfunction "S_P$2") (pintype "passive"))
    )
    (net (code "108") (name "POTS2") (class "Default")
      (node (ref "IC8") (pin "38") (pinfunction "(ADC2)PA2_38") (pintype "bidirectional"))
      (node (ref "R38") (pin "P$2") (pinfunction "S_P$2") (pintype "passive"))
    )
    (net (code "109") (name "POTS3") (class "Default")
      (node (ref "IC8") (pin "37") (pinfunction "(ADC3)PA3_37") (pintype "bidirectional"))
      (node (ref "R37") (pin "P$2") (pinfunction "S_P$2") (pintype "passive"))
    )
    (net (code "110") (name "POTS4") (class "Default")
      (node (ref "IC8") (pin "36") (pinfunction "(ADC4)PA4_36") (pintype "bidirectional"))
      (node (ref "R28") (pin "P$2") (pinfunction "S_P$2") (pintype "passive"))
    )
    (net (code "111") (name "POTS5") (class "Default")
      (node (ref "IC8") (pin "35") (pinfunction "(ADC5)PA5_35") (pintype "bidirectional"))
      (node (ref "R29") (pin "P$2") (pinfunction "S_P$2") (pintype "passive"))
    )
    (net (code "112") (name "POTS6") (class "Default")
      (node (ref "IC8") (pin "34") (pinfunction "(ADC6)PA6_34") (pintype "bidirectional"))
      (node (ref "R30") (pin "P$2") (pinfunction "S_P$2") (pintype "passive"))
    )
    (net (code "113") (name "POTS7") (class "Default")
      (node (ref "IC8") (pin "33") (pinfunction "(ADC7)PA7_33") (pintype "bidirectional"))
      (node (ref "R31") (pin "P$2") (pinfunction "S_P$2") (pintype "passive"))
    )
    (net (code "114") (name "RESET") (class "Default")
      (node (ref "C17") (pin "1") (pinfunction "1_1") (pintype "passive"))
      (node (ref "IC8") (pin "9") (pinfunction "RESET_9") (pintype "input"))
      (node (ref "R16") (pin "1") (pinfunction "1_1") (pintype "passive"))
      (node (ref "U1") (pin "5") (pinfunction "5_5") (pintype "passive"))
    )
    (net (code "115") (name "RS0") (class "Default")
      (node (ref "J3") (pin "TN") (pinfunction "TN_TN") (pintype "passive"))
      (node (ref "RN1") (pin "2") (pinfunction "2_2") (pintype "passive"))
    )
    (net (code "116") (name "RS1") (class "Default")
      (node (ref "J4") (pin "TN") (pinfunction "TN_TN") (pintype "passive"))
      (node (ref "RN1") (pin "3") (pinfunction "3_3") (pintype "passive"))
    )
    (net (code "117") (name "RS2") (class "Default")
      (node (ref "J5") (pin "TN") (pinfunction "TN_TN") (pintype "passive"))
      (node (ref "RN1") (pin "4") (pinfunction "4_4") (pintype "passive"))
    )
    (net (code "118") (name "RS3") (class "Default")
      (node (ref "J6") (pin "TN") (pinfunction "TN_TN") (pintype "passive"))
      (node (ref "RN1") (pin "5") (pinfunction "5_5") (pintype "passive"))
    )
    (net (code "119") (name "RS4") (class "Default")
      (node (ref "J7") (pin "TN") (pinfunction "TN_TN") (pintype "passive"))
      (node (ref "RN1") (pin "6") (pinfunction "6_6") (pintype "passive"))
    )
    (net (code "120") (name "RS5") (class "Default")
      (node (ref "J8") (pin "TN") (pinfunction "TN_TN") (pintype "passive"))
      (node (ref "RN1") (pin "7") (pinfunction "7_7") (pintype "passive"))
    )
    (net (code "121") (name "SCK") (class "Default")
      (node (ref "IC3") (pin "5") (pinfunction "I_5") (pintype "input"))
      (node (ref "IC8") (pin "8") (pinfunction "(SCK)PB7_8") (pintype "bidirectional"))
      (node (ref "JP2") (pin "5") (pinfunction "5_5") (pintype "passive"))
      (node (ref "JP4") (pin "5") (pinfunction "5_5") (pintype "passive"))
      (node (ref "JP6") (pin "5") (pinfunction "5_5") (pintype "passive"))
      (node (ref "JP7") (pin "1") (pinfunction "1_1") (pintype "passive"))
      (node (ref "U1") (pin "3") (pinfunction "3_3") (pintype "passive"))
    )
    (net (code "122") (name "SS") (class "Default")
      (node (ref "IC4") (pin "4") (pinfunction "G2A_4") (pintype "input"))
      (node (ref "IC8") (pin "5") (pinfunction "(SS)PB4_5") (pintype "bidirectional"))
    )
    (net (code "123") (name "SS0") (class "Default")
      (node (ref "IC4") (pin "15") (pinfunction "Y0_15") (pintype "output"))
      (node (ref "JP2") (pin "1") (pinfunction "1_1") (pintype "passive"))
    )
    (net (code "124") (name "SS1") (class "Default")
      (node (ref "IC4") (pin "14") (pinfunction "Y1_14") (pintype "output"))
      (node (ref "JP2") (pin "2") (pinfunction "2_2") (pintype "passive"))
    )
    (net (code "125") (name "SS2") (class "Default")
      (node (ref "IC4") (pin "13") (pinfunction "Y2_13") (pintype "output"))
      (node (ref "JP4") (pin "1") (pinfunction "1_1") (pintype "passive"))
    )
    (net (code "126") (name "SS3") (class "Default")
      (node (ref "IC4") (pin "12") (pinfunction "Y3_12") (pintype "output"))
      (node (ref "JP4") (pin "2") (pinfunction "2_2") (pintype "passive"))
    )
    (net (code "127") (name "SS4") (class "Default")
      (node (ref "IC4") (pin "11") (pinfunction "Y4_11") (pintype "output"))
      (node (ref "JP6") (pin "1") (pinfunction "1_1") (pintype "passive"))
    )
    (net (code "128") (name "SS5") (class "Default")
      (node (ref "IC4") (pin "10") (pinfunction "Y5_10") (pintype "output"))
      (node (ref "JP6") (pin "2") (pinfunction "2_2") (pintype "passive"))
    )
    (net (code "129") (name "SS6") (class "Default")
      (node (ref "IC4") (pin "9") (pinfunction "Y6_9") (pintype "output"))
      (node (ref "JP7") (pin "4") (pinfunction "4_4") (pintype "passive"))
    )
    (net (code "130") (name "SS7") (class "Default")
      (node (ref "IC3") (pin "7") (pinfunction "I_7") (pintype "input"))
      (node (ref "IC4") (pin "7") (pinfunction "Y7_7") (pintype "output"))
    )
    (net (code "131") (name "SS_ADDR0") (class "Default")
      (node (ref "IC4") (pin "1") (pinfunction "A_1") (pintype "input"))
      (node (ref "IC8") (pin "1") (pinfunction "(T0/XCK)PB0_1") (pintype "bidirectional"))
    )
    (net (code "132") (name "SS_ADDR1") (class "Default")
      (node (ref "IC4") (pin "2") (pinfunction "B_2") (pintype "input"))
      (node (ref "IC8") (pin "2") (pinfunction "(T1)PB1_2") (pintype "bidirectional"))
    )
    (net (code "133") (name "SS_ADDR2") (class "Default")
      (node (ref "IC4") (pin "3") (pinfunction "C_3") (pintype "input"))
      (node (ref "IC8") (pin "3") (pinfunction "(AIN0/INT2)PB2_3") (pintype "bidirectional"))
    )
    (net (code "134") (name "VCC") (class "Default")
      (node (ref "C16") (pin "+") (pinfunction "+_+") (pintype "passive"))
      (node (ref "C3") (pin "1") (pinfunction "1_1") (pintype "passive"))
      (node (ref "D6") (pin "A") (pinfunction "A_A") (pintype "passive"))
      (node (ref "D7") (pin "C") (pinfunction "C_C") (pintype "passive"))
      (node (ref "IC1") (pin "8") (pinfunction "V+_8") (pintype "power_in"))
      (node (ref "IC6") (pin "OUT") (pinfunction "OUT_OUT") (pintype "passive"))
      (node (ref "JP1") (pin "3") (pinfunction "3_3") (pintype "passive"))
      (node (ref "JP3") (pin "3") (pinfunction "3_3") (pintype "passive"))
      (node (ref "JP5") (pin "3") (pinfunction "3_3") (pintype "passive"))
    )
    (net (code "135") (name "VEE") (class "Default")
      (node (ref "C14") (pin "-") (pinfunction "-_-") (pintype "passive"))
      (node (ref "C7") (pin "2") (pinfunction "2_2") (pintype "passive"))
      (node (ref "D4") (pin "C") (pinfunction "C_C") (pintype "passive"))
      (node (ref "D5") (pin "A") (pinfunction "A_A") (pintype "passive"))
      (node (ref "IC1") (pin "4") (pinfunction "V-_4") (pintype "power_in"))
      (node (ref "IC5") (pin "OUT") (pinfunction "OUT_OUT") (pintype "passive"))
      (node (ref "JP1") (pin "5") (pinfunction "5_5") (pintype "passive"))
      (node (ref "JP3") (pin "5") (pinfunction "5_5") (pintype "passive"))
      (node (ref "JP5") (pin "5") (pinfunction "5_5") (pintype "passive"))
    )
    (net (code "136") (name "unconnected-(IC3D-O-Pad10)") (class "Default")
      (node (ref "IC3") (pin "10") (pinfunction "O_10") (pintype "output"))
    )
    (net (code "137") (name "unconnected-(IC3E-O-Pad12)") (class "Default")
      (node (ref "IC3") (pin "12") (pinfunction "O_12") (pintype "output"))
    )
    (net (code "138") (name "unconnected-(IC3F-O-Pad15)") (class "Default")
      (node (ref "IC3") (pin "15") (pinfunction "O_15") (pintype "output"))
    )
    (net (code "139") (name "unconnected-(IC8-(AIN1{slash}OC0)PB3-Pad4)") (class "Default")
      (node (ref "IC8") (pin "4") (pinfunction "(AIN1/OC0)PB3_4") (pintype "bidirectional"))
    )
    (net (code "140") (name "unconnected-(IC8-(SCL)PC0-Pad22)") (class "Default")
      (node (ref "IC8") (pin "22") (pinfunction "(SCL)PC0_22") (pintype "bidirectional"))
    )
    (net (code "141") (name "unconnected-(IC9A-~{QH}-Pad7)") (class "Default")
      (node (ref "IC9") (pin "7") (pinfunction "~{QH}_7") (pintype "output"))
    )
    (net (code "142") (name "unconnected-(IC10A-QH*-Pad9)") (class "Default")
      (node (ref "IC10") (pin "9") (pinfunction "QH*_9") (pintype "tri_state"))
    )
    (net (code "143") (name "unconnected-(J1-Pad2)") (class "Default")
      (node (ref "J1") (pin "2") (pinfunction "2_2") (pintype "passive"))
    )
    (net (code "144") (name "unconnected-(J2-PadTN)") (class "Default")
      (node (ref "J2") (pin "TN") (pinfunction "TN_TN") (pintype "passive"))
    )
    (net (code "145") (name "unconnected-(OK1-VB-Pad7)") (class "Default")
      (node (ref "OK1") (pin "7") (pinfunction "VB_7") (pintype "passive"))
    )
    (net (code "146") (name "unconnected-(U$22-DB0-Pad7)") (class "Default")
      (node (ref "U$22") (pin "7") (pinfunction "DB0_7") (pintype "bidirectional"))
    )
    (net (code "147") (name "unconnected-(U$22-DB1-Pad8)") (class "Default")
      (node (ref "U$22") (pin "8") (pinfunction "DB1_8") (pintype "bidirectional"))
    )
    (net (code "148") (name "unconnected-(U$22-DB2-Pad9)") (class "Default")
      (node (ref "U$22") (pin "9") (pinfunction "DB2_9") (pintype "bidirectional"))
    )
    (net (code "149") (name "unconnected-(U$22-DB3-Pad10)") (class "Default")
      (node (ref "U$22") (pin "10") (pinfunction "DB3_10") (pintype "bidirectional"))
    )
    (net (code "150") (name "unconnected-(U$26-CARD_DETECT-PadCD)") (class "Default")
      (node (ref "U$26") (pin "CD") (pinfunction "CARD_DETECT_CD") (pintype "passive"))
    )
    (net (code "151") (name "unconnected-(U$26-DAT1-Pad8)") (class "Default")
      (node (ref "U$26") (pin "8") (pinfunction "DAT1_8") (pintype "bidirectional"))
    )
    (net (code "152") (name "unconnected-(U$26-DAT2-Pad9)") (class "Default")
      (node (ref "U$26") (pin "9") (pinfunction "DAT2_9") (pintype "bidirectional"))
    )
    (net (code "153") (name "unconnected-(U$26-WRITE_PROTECT-PadWP)") (class "Default")
      (node (ref "U$26") (pin "WP") (pinfunction "WRITE_PROTECT_WP") (pintype "passive"))
    )
    (net (code "154") (name "unconnected-(X1-Pad1)") (class "Default")
      (node (ref "X1") (pin "1") (pinfunction "1_1") (pintype "passive"))
    )
    (net (code "155") (name "unconnected-(X1-Pad2)") (class "Default")
      (node (ref "X1") (pin "2") (pinfunction "2_2") (pintype "passive"))
    )
    (net (code "156") (name "unconnected-(X1-Pad3)") (class "Default")
      (node (ref "X1") (pin "3") (pinfunction "3_3") (pintype "passive"))
    )
    (net (code "157") (name "unconnected-(X2-Pad1)") (class "Default")
      (node (ref "X2") (pin "1") (pinfunction "1_1") (pintype "passive"))
    )
    (net (code "158") (name "unconnected-(X2-Pad3)") (class "Default")
      (node (ref "X2") (pin "3") (pinfunction "3_3") (pintype "passive"))
    )
  )
)
